# main_board.net
KiCad netlist of a schematic drawn in EAGLE
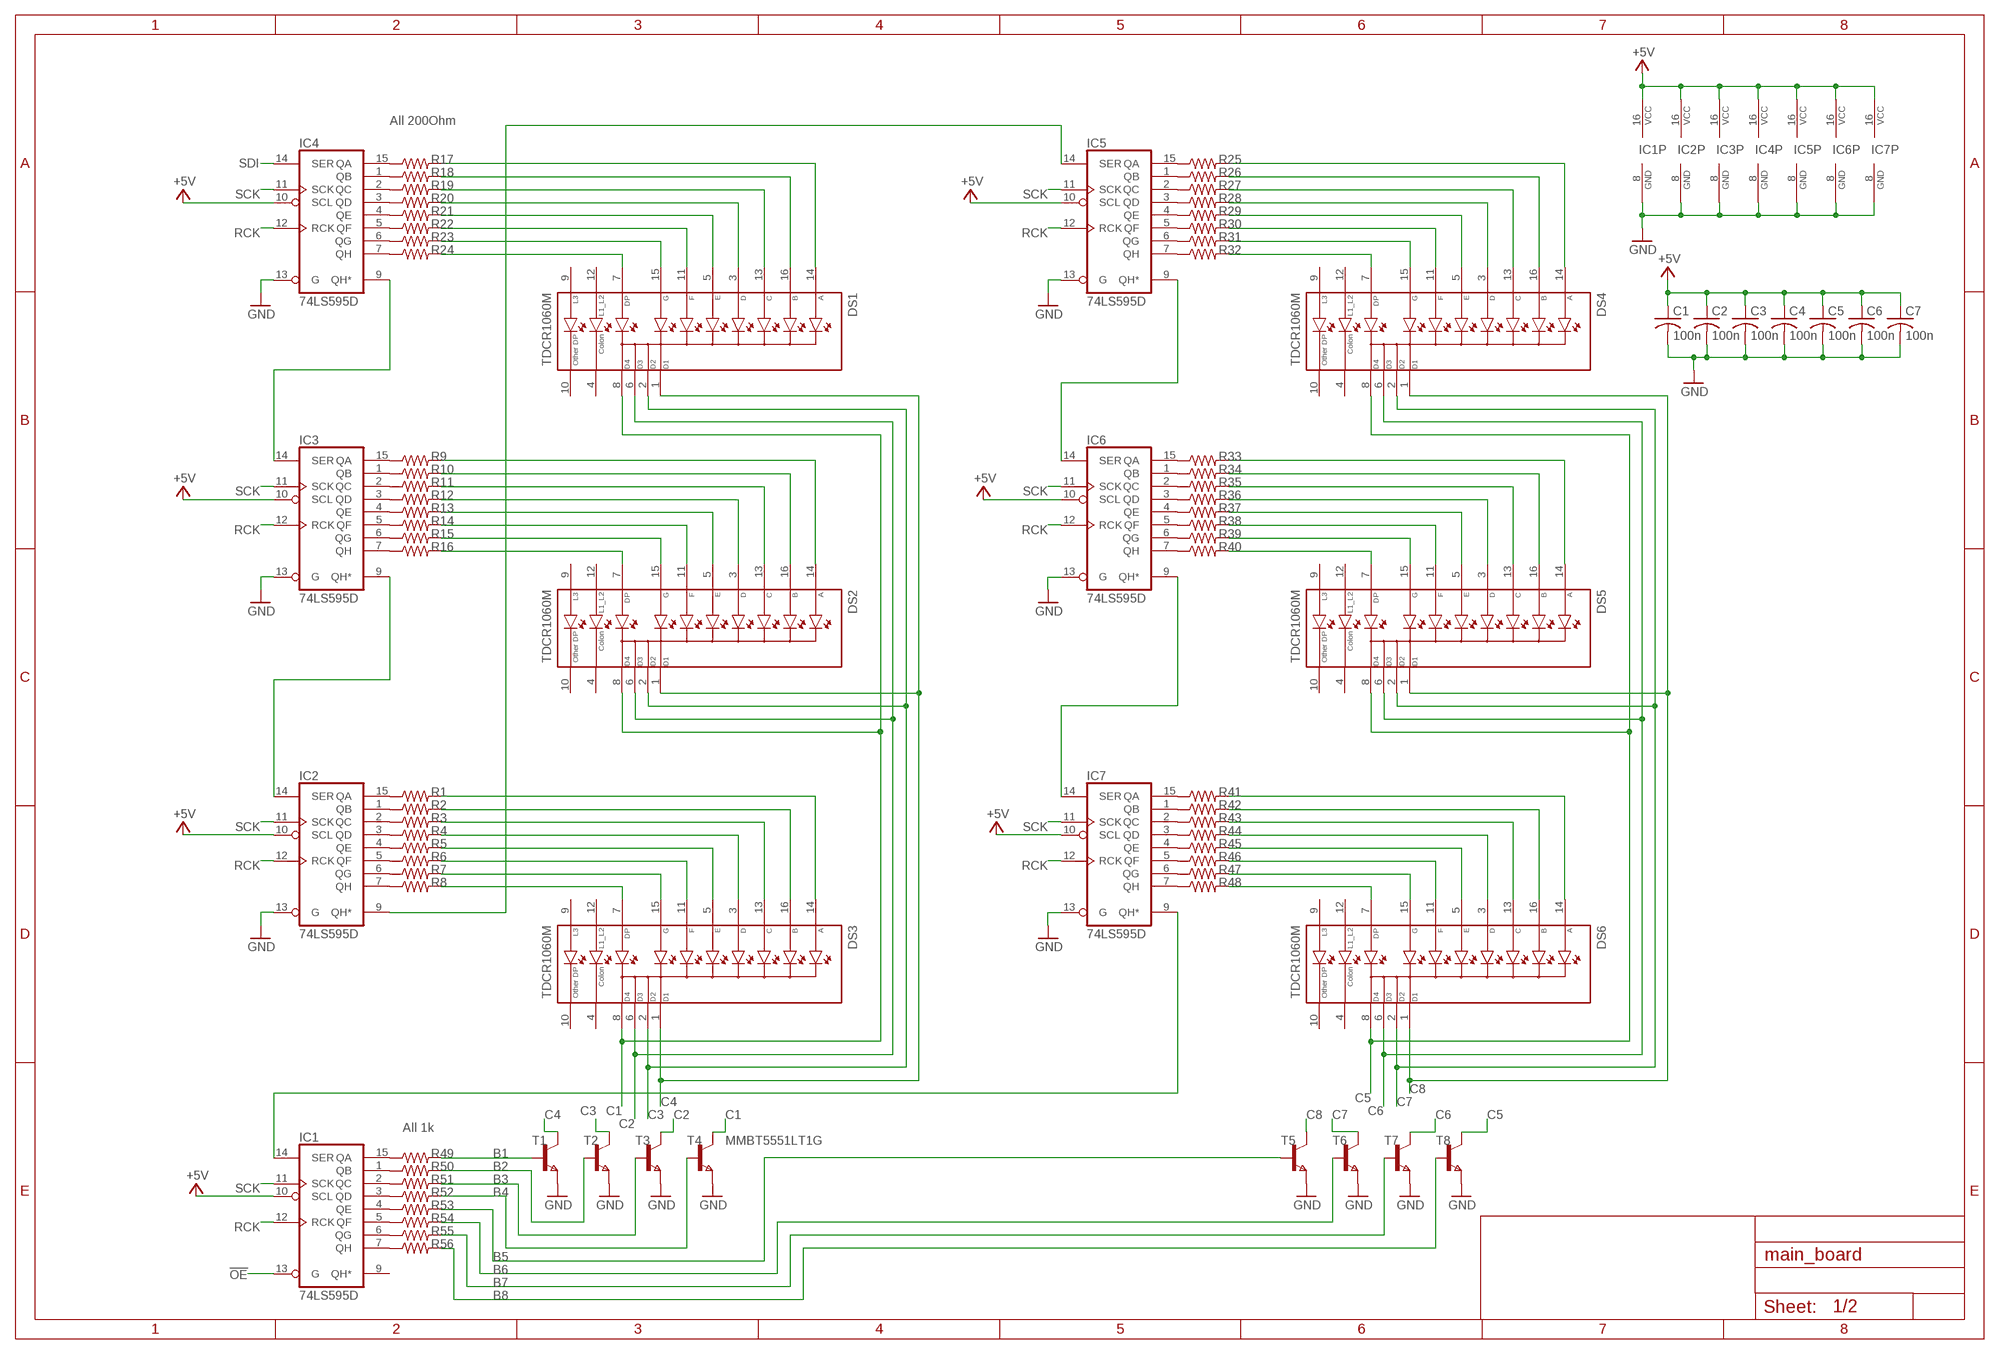
[diagram p0: schematic, sheet 1]
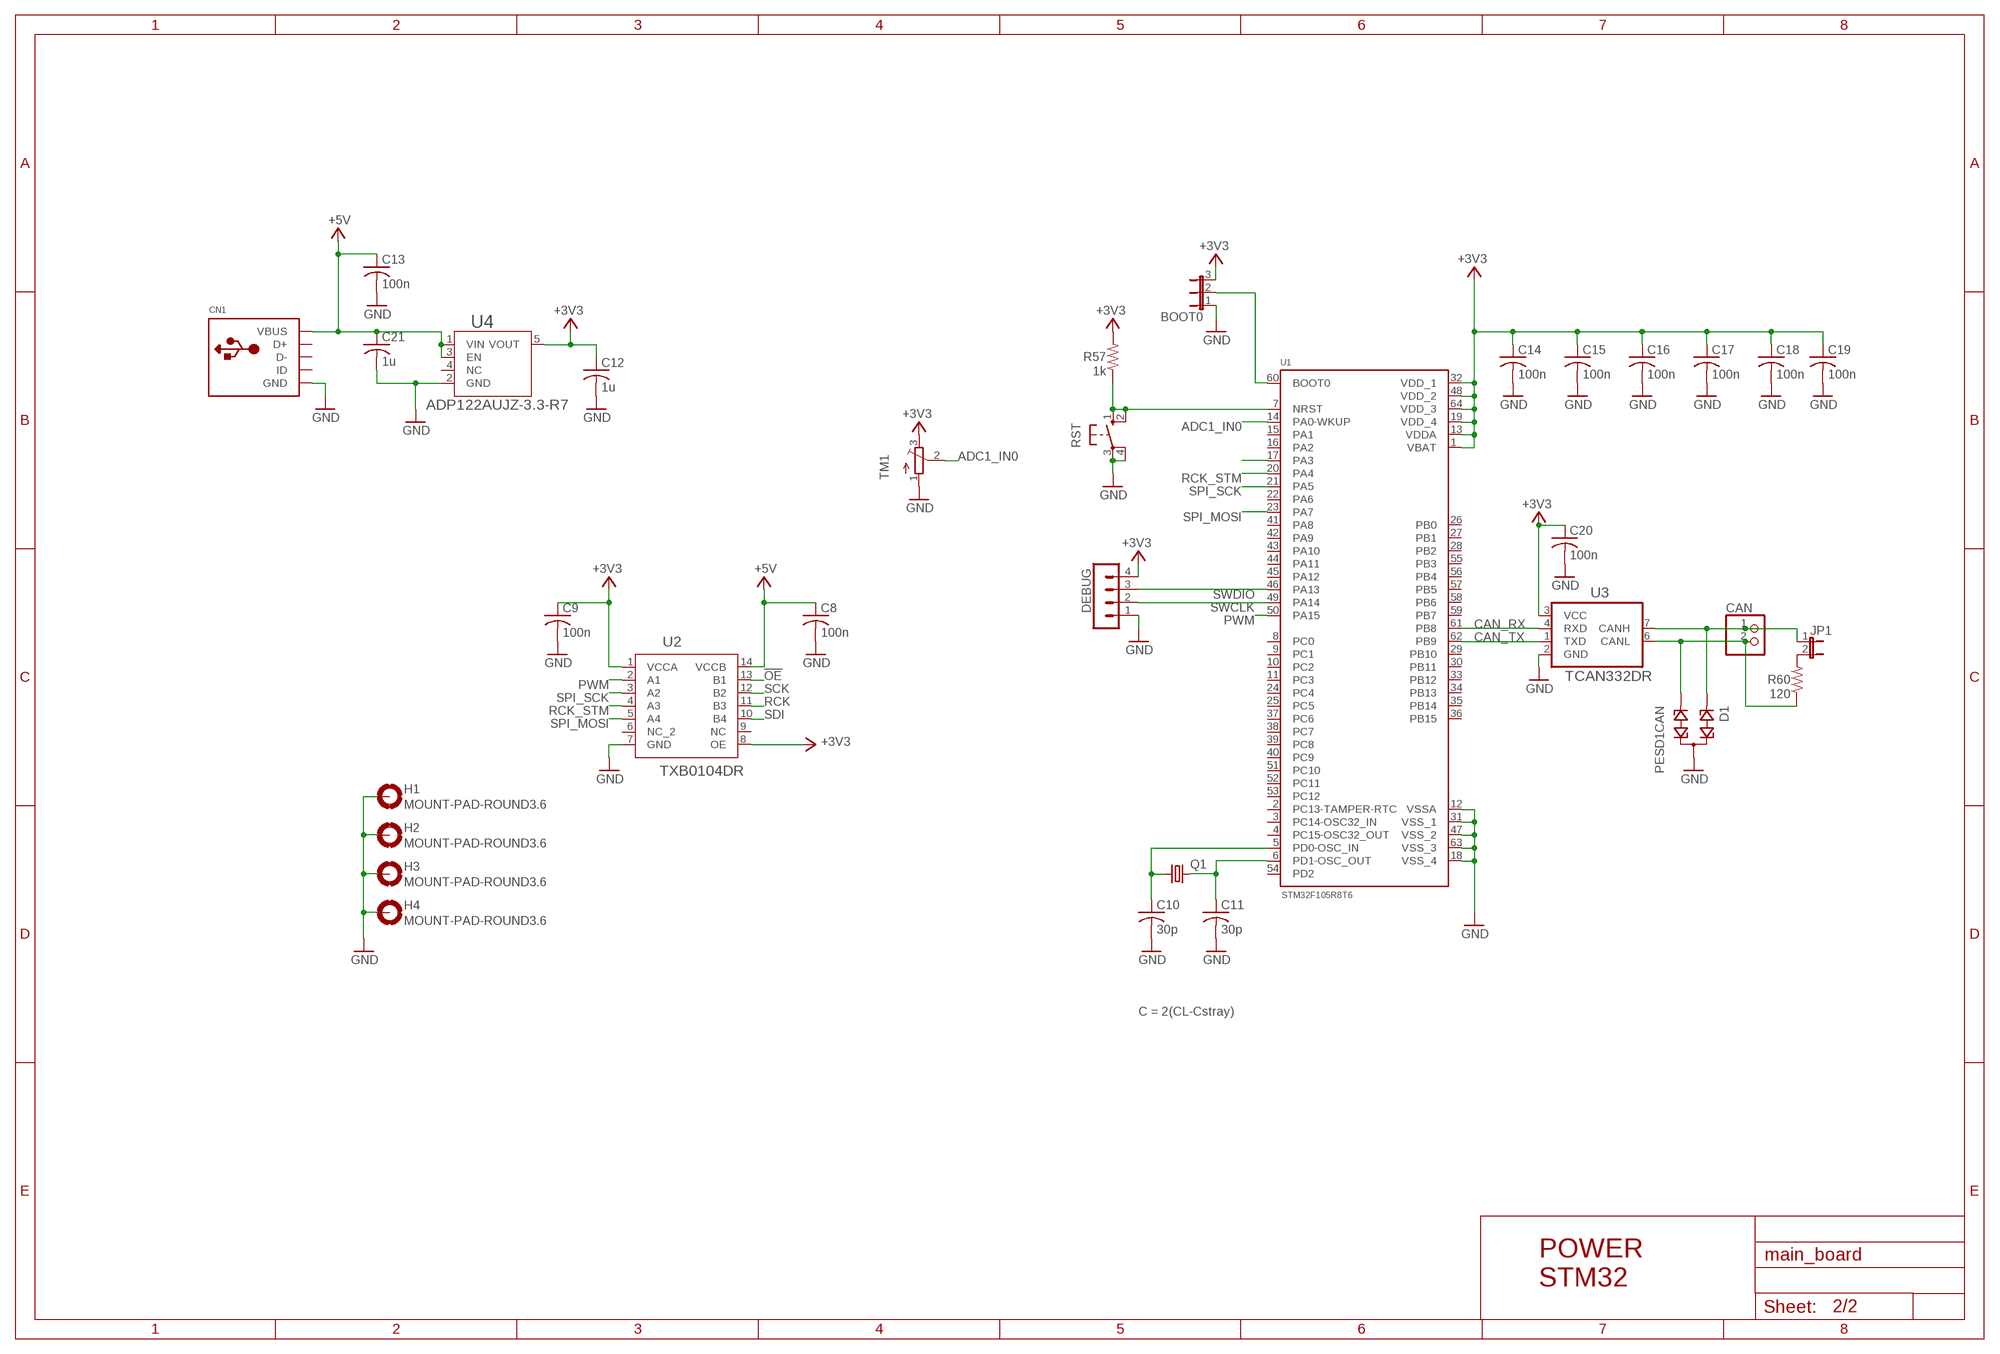
[diagram p1: schematic, sheet 2]

(export (version "E")
  (design (tool "Eeschema 10.0.6"))
  (components
    (comp (ref "C1")
      (value "100n")
      (footprint "eagle-import:C0603")
      (libsource (lib "eagle-import") (part "C-USC0603"))
    )
    (comp (ref "C2")
      (value "100n")
      (footprint "eagle-import:C0603")
      (libsource (lib "eagle-import") (part "C-USC0603"))
    )
    (comp (ref "C3")
      (value "100n")
      (footprint "eagle-import:C0603")
      (libsource (lib "eagle-import") (part "C-USC0603"))
    )
    (comp (ref "C4")
      (value "100n")
      (footprint "eagle-import:C0603")
      (libsource (lib "eagle-import") (part "C-USC0603"))
    )
    (comp (ref "C5")
      (value "100n")
      (footprint "eagle-import:C0603")
      (libsource (lib "eagle-import") (part "C-USC0603"))
    )
    (comp (ref "C6")
      (value "100n")
      (footprint "eagle-import:C0603")
      (libsource (lib "eagle-import") (part "C-USC0603"))
    )
    (comp (ref "C7")
      (value "100n")
      (footprint "eagle-import:C0603")
      (libsource (lib "eagle-import") (part "C-USC0603"))
    )
    (comp (ref "DS1")
      (value "TDCR1060M")
      (footprint "eagle-import:DISPLAY_TDCR1060M")
      (fields (field (name "DIGIKEY_PART_NUMBER") "TDCR1060M-ND") (field (name "MF") "Vishay Semiconductor"))
      (libsource (lib "eagle-import") (part "TDCR1060M"))
    )
    (comp (ref "DS2")
      (value "TDCR1060M")
      (footprint "eagle-import:DISPLAY_TDCR1060M")
      (fields (field (name "DIGIKEY_PART_NUMBER") "TDCR1060M-ND") (field (name "MF") "Vishay Semiconductor"))
      (libsource (lib "eagle-import") (part "TDCR1060M"))
    )
    (comp (ref "DS3")
      (value "TDCR1060M")
      (footprint "eagle-import:DISPLAY_TDCR1060M")
      (fields (field (name "DIGIKEY_PART_NUMBER") "TDCR1060M-ND") (field (name "MF") "Vishay Semiconductor"))
      (libsource (lib "eagle-import") (part "TDCR1060M"))
    )
    (comp (ref "DS4")
      (value "TDCR1060M")
      (footprint "eagle-import:DISPLAY_TDCR1060M")
      (fields (field (name "DIGIKEY_PART_NUMBER") "TDCR1060M-ND") (field (name "MF") "Vishay Semiconductor"))
      (libsource (lib "eagle-import") (part "TDCR1060M"))
    )
    (comp (ref "DS5")
      (value "TDCR1060M")
      (footprint "eagle-import:DISPLAY_TDCR1060M")
      (fields (field (name "DIGIKEY_PART_NUMBER") "TDCR1060M-ND") (field (name "MF") "Vishay Semiconductor"))
      (libsource (lib "eagle-import") (part "TDCR1060M"))
    )
    (comp (ref "DS6")
      (value "TDCR1060M")
      (footprint "eagle-import:DISPLAY_TDCR1060M")
      (fields (field (name "DIGIKEY_PART_NUMBER") "TDCR1060M-ND") (field (name "MF") "Vishay Semiconductor"))
      (libsource (lib "eagle-import") (part "TDCR1060M"))
    )
    (comp (ref "IC1")
      (value "74LS595D")
      (footprint "eagle-import:SO16")
      (libsource (lib "eagle-import") (part "74595DLS"))
    )
    (comp (ref "IC2")
      (value "74LS595D")
      (footprint "eagle-import:SO16")
      (libsource (lib "eagle-import") (part "74595DLS"))
    )
    (comp (ref "IC3")
      (value "74LS595D")
      (footprint "eagle-import:SO16")
      (libsource (lib "eagle-import") (part "74595DLS"))
    )
    (comp (ref "IC4")
      (value "74LS595D")
      (footprint "eagle-import:SO16")
      (libsource (lib "eagle-import") (part "74595DLS"))
    )
    (comp (ref "IC5")
      (value "74LS595D")
      (footprint "eagle-import:SO16")
      (libsource (lib "eagle-import") (part "74595DLS"))
    )
    (comp (ref "IC6")
      (value "74LS595D")
      (footprint "eagle-import:SO16")
      (libsource (lib "eagle-import") (part "74595DLS"))
    )
    (comp (ref "IC7")
      (value "74LS595D")
      (footprint "eagle-import:SO16")
      (libsource (lib "eagle-import") (part "74595DLS"))
    )
    (comp (ref "R1")
      (value "R-US_R0603")
      (footprint "eagle-import:R0603")
      (libsource (lib "eagle-import") (part "R-US_R0603"))
    )
    (comp (ref "R2")
      (value "R-US_R0603")
      (footprint "eagle-import:R0603")
      (libsource (lib "eagle-import") (part "R-US_R0603"))
    )
    (comp (ref "R3")
      (value "R-US_R0603")
      (footprint "eagle-import:R0603")
      (libsource (lib "eagle-import") (part "R-US_R0603"))
    )
    (comp (ref "R4")
      (value "R-US_R0603")
      (footprint "eagle-import:R0603")
      (libsource (lib "eagle-import") (part "R-US_R0603"))
    )
    (comp (ref "R5")
      (value "R-US_R0603")
      (footprint "eagle-import:R0603")
      (libsource (lib "eagle-import") (part "R-US_R0603"))
    )
    (comp (ref "R6")
      (value "R-US_R0603")
      (footprint "eagle-import:R0603")
      (libsource (lib "eagle-import") (part "R-US_R0603"))
    )
    (comp (ref "R7")
      (value "R-US_R0603")
      (footprint "eagle-import:R0603")
      (libsource (lib "eagle-import") (part "R-US_R0603"))
    )
    (comp (ref "R8")
      (value "R-US_R0603")
      (footprint "eagle-import:R0603")
      (libsource (lib "eagle-import") (part "R-US_R0603"))
    )
    (comp (ref "R9")
      (value "R-US_R0603")
      (footprint "eagle-import:R0603")
      (libsource (lib "eagle-import") (part "R-US_R0603"))
    )
    (comp (ref "R10")
      (value "R-US_R0603")
      (footprint "eagle-import:R0603")
      (libsource (lib "eagle-import") (part "R-US_R0603"))
    )
    (comp (ref "R11")
      (value "R-US_R0603")
      (footprint "eagle-import:R0603")
      (libsource (lib "eagle-import") (part "R-US_R0603"))
    )
    (comp (ref "R12")
      (value "R-US_R0603")
      (footprint "eagle-import:R0603")
      (libsource (lib "eagle-import") (part "R-US_R0603"))
    )
    (comp (ref "R13")
      (value "R-US_R0603")
      (footprint "eagle-import:R0603")
      (libsource (lib "eagle-import") (part "R-US_R0603"))
    )
    (comp (ref "R14")
      (value "R-US_R0603")
      (footprint "eagle-import:R0603")
      (libsource (lib "eagle-import") (part "R-US_R0603"))
    )
    (comp (ref "R15")
      (value "R-US_R0603")
      (footprint "eagle-import:R0603")
      (libsource (lib "eagle-import") (part "R-US_R0603"))
    )
    (comp (ref "R16")
      (value "R-US_R0603")
      (footprint "eagle-import:R0603")
      (libsource (lib "eagle-import") (part "R-US_R0603"))
    )
    (comp (ref "R17")
      (value "R-US_R0603")
      (footprint "eagle-import:R0603")
      (libsource (lib "eagle-import") (part "R-US_R0603"))
    )
    (comp (ref "R18")
      (value "R-US_R0603")
      (footprint "eagle-import:R0603")
      (libsource (lib "eagle-import") (part "R-US_R0603"))
    )
    (comp (ref "R19")
      (value "R-US_R0603")
      (footprint "eagle-import:R0603")
      (libsource (lib "eagle-import") (part "R-US_R0603"))
    )
    (comp (ref "R20")
      (value "R-US_R0603")
      (footprint "eagle-import:R0603")
      (libsource (lib "eagle-import") (part "R-US_R0603"))
    )
    (comp (ref "R21")
      (value "R-US_R0603")
      (footprint "eagle-import:R0603")
      (libsource (lib "eagle-import") (part "R-US_R0603"))
    )
    (comp (ref "R22")
      (value "R-US_R0603")
      (footprint "eagle-import:R0603")
      (libsource (lib "eagle-import") (part "R-US_R0603"))
    )
    (comp (ref "R23")
      (value "R-US_R0603")
      (footprint "eagle-import:R0603")
      (libsource (lib "eagle-import") (part "R-US_R0603"))
    )
    (comp (ref "R24")
      (value "R-US_R0603")
      (footprint "eagle-import:R0603")
      (libsource (lib "eagle-import") (part "R-US_R0603"))
    )
    (comp (ref "R25")
      (value "R-US_R0603")
      (footprint "eagle-import:R0603")
      (libsource (lib "eagle-import") (part "R-US_R0603"))
    )
    (comp (ref "R26")
      (value "R-US_R0603")
      (footprint "eagle-import:R0603")
      (libsource (lib "eagle-import") (part "R-US_R0603"))
    )
    (comp (ref "R27")
      (value "R-US_R0603")
      (footprint "eagle-import:R0603")
      (libsource (lib "eagle-import") (part "R-US_R0603"))
    )
    (comp (ref "R28")
      (value "R-US_R0603")
      (footprint "eagle-import:R0603")
      (libsource (lib "eagle-import") (part "R-US_R0603"))
    )
    (comp (ref "R29")
      (value "R-US_R0603")
      (footprint "eagle-import:R0603")
      (libsource (lib "eagle-import") (part "R-US_R0603"))
    )
    (comp (ref "R30")
      (value "R-US_R0603")
      (footprint "eagle-import:R0603")
      (libsource (lib "eagle-import") (part "R-US_R0603"))
    )
    (comp (ref "R31")
      (value "R-US_R0603")
      (footprint "eagle-import:R0603")
      (libsource (lib "eagle-import") (part "R-US_R0603"))
    )
    (comp (ref "R32")
      (value "R-US_R0603")
      (footprint "eagle-import:R0603")
      (libsource (lib "eagle-import") (part "R-US_R0603"))
    )
    (comp (ref "R33")
      (value "R-US_R0603")
      (footprint "eagle-import:R0603")
      (libsource (lib "eagle-import") (part "R-US_R0603"))
    )
    (comp (ref "R34")
      (value "R-US_R0603")
      (footprint "eagle-import:R0603")
      (libsource (lib "eagle-import") (part "R-US_R0603"))
    )
    (comp (ref "R35")
      (value "R-US_R0603")
      (footprint "eagle-import:R0603")
      (libsource (lib "eagle-import") (part "R-US_R0603"))
    )
    (comp (ref "R36")
      (value "R-US_R0603")
      (footprint "eagle-import:R0603")
      (libsource (lib "eagle-import") (part "R-US_R0603"))
    )
    (comp (ref "R37")
      (value "R-US_R0603")
      (footprint "eagle-import:R0603")
      (libsource (lib "eagle-import") (part "R-US_R0603"))
    )
    (comp (ref "R38")
      (value "R-US_R0603")
      (footprint "eagle-import:R0603")
      (libsource (lib "eagle-import") (part "R-US_R0603"))
    )
    (comp (ref "R39")
      (value "R-US_R0603")
      (footprint "eagle-import:R0603")
      (libsource (lib "eagle-import") (part "R-US_R0603"))
    )
    (comp (ref "R40")
      (value "R-US_R0603")
      (footprint "eagle-import:R0603")
      (libsource (lib "eagle-import") (part "R-US_R0603"))
    )
    (comp (ref "R41")
      (value "R-US_R0603")
      (footprint "eagle-import:R0603")
      (libsource (lib "eagle-import") (part "R-US_R0603"))
    )
    (comp (ref "R42")
      (value "R-US_R0603")
      (footprint "eagle-import:R0603")
      (libsource (lib "eagle-import") (part "R-US_R0603"))
    )
    (comp (ref "R43")
      (value "R-US_R0603")
      (footprint "eagle-import:R0603")
      (libsource (lib "eagle-import") (part "R-US_R0603"))
    )
    (comp (ref "R44")
      (value "R-US_R0603")
      (footprint "eagle-import:R0603")
      (libsource (lib "eagle-import") (part "R-US_R0603"))
    )
    (comp (ref "R45")
      (value "R-US_R0603")
      (footprint "eagle-import:R0603")
      (libsource (lib "eagle-import") (part "R-US_R0603"))
    )
    (comp (ref "R46")
      (value "R-US_R0603")
      (footprint "eagle-import:R0603")
      (libsource (lib "eagle-import") (part "R-US_R0603"))
    )
    (comp (ref "R47")
      (value "R-US_R0603")
      (footprint "eagle-import:R0603")
      (libsource (lib "eagle-import") (part "R-US_R0603"))
    )
    (comp (ref "R48")
      (value "R-US_R0603")
      (footprint "eagle-import:R0603")
      (libsource (lib "eagle-import") (part "R-US_R0603"))
    )
    (comp (ref "R49")
      (value "R-US_R0603")
      (footprint "eagle-import:R0603")
      (libsource (lib "eagle-import") (part "R-US_R0603"))
    )
    (comp (ref "R50")
      (value "R-US_R0603")
      (footprint "eagle-import:R0603")
      (libsource (lib "eagle-import") (part "R-US_R0603"))
    )
    (comp (ref "R51")
      (value "R-US_R0603")
      (footprint "eagle-import:R0603")
      (libsource (lib "eagle-import") (part "R-US_R0603"))
    )
    (comp (ref "R52")
      (value "R-US_R0603")
      (footprint "eagle-import:R0603")
      (libsource (lib "eagle-import") (part "R-US_R0603"))
    )
    (comp (ref "R53")
      (value "R-US_R0603")
      (footprint "eagle-import:R0603")
      (libsource (lib "eagle-import") (part "R-US_R0603"))
    )
    (comp (ref "R54")
      (value "R-US_R0603")
      (footprint "eagle-import:R0603")
      (libsource (lib "eagle-import") (part "R-US_R0603"))
    )
    (comp (ref "R55")
      (value "R-US_R0603")
      (footprint "eagle-import:R0603")
      (libsource (lib "eagle-import") (part "R-US_R0603"))
    )
    (comp (ref "R56")
      (value "R-US_R0603")
      (footprint "eagle-import:R0603")
      (libsource (lib "eagle-import") (part "R-US_R0603"))
    )
    (comp (ref "T1")
      (value "NPNSOT23")
      (footprint "eagle-import:SOT-23")
      (fields (field (name "MPN") "DSS20201L-7"))
      (libsource (lib "eagle-import") (part "NPNSOT23"))
    )
    (comp (ref "T2")
      (value "NPNSOT23")
      (footprint "eagle-import:SOT-23")
      (fields (field (name "MPN") "DSS20201L-7"))
      (libsource (lib "eagle-import") (part "NPNSOT23"))
    )
    (comp (ref "T3")
      (value "NPNSOT23")
      (footprint "eagle-import:SOT-23")
      (fields (field (name "MPN") "DSS20201L-7"))
      (libsource (lib "eagle-import") (part "NPNSOT23"))
    )
    (comp (ref "T4")
      (value "NPNSOT23")
      (footprint "eagle-import:SOT-23")
      (fields (field (name "MPN") "DSS20201L-7"))
      (libsource (lib "eagle-import") (part "NPNSOT23"))
    )
    (comp (ref "T5")
      (value "NPNSOT23")
      (footprint "eagle-import:SOT-23")
      (fields (field (name "MPN") "DSS20201L-7"))
      (libsource (lib "eagle-import") (part "NPNSOT23"))
    )
    (comp (ref "T6")
      (value "NPNSOT23")
      (footprint "eagle-import:SOT-23")
      (fields (field (name "MPN") "DSS20201L-7"))
      (libsource (lib "eagle-import") (part "NPNSOT23"))
    )
    (comp (ref "T7")
      (value "NPNSOT23")
      (footprint "eagle-import:SOT-23")
      (fields (field (name "MPN") "DSS20201L-7"))
      (libsource (lib "eagle-import") (part "NPNSOT23"))
    )
    (comp (ref "T8")
      (value "NPNSOT23")
      (footprint "eagle-import:SOT-23")
      (fields (field (name "MPN") "DSS20201L-7"))
      (libsource (lib "eagle-import") (part "NPNSOT23"))
    )
    (comp (ref "BOOT0")
      (value "JP2E")
      (footprint "eagle-import:JP2")
      (libsource (lib "eagle-import") (part "JP2E"))
    )
    (comp (ref "C8")
      (value "100n")
      (footprint "eagle-import:C0603")
      (libsource (lib "eagle-import") (part "C-USC0603"))
    )
    (comp (ref "C9")
      (value "100n")
      (footprint "eagle-import:C0603")
      (libsource (lib "eagle-import") (part "C-USC0603"))
    )
    (comp (ref "C10")
      (value "30p")
      (footprint "eagle-import:C0603")
      (libsource (lib "eagle-import") (part "C-USC0603"))
    )
    (comp (ref "C11")
      (value "30p")
      (footprint "eagle-import:C0603")
      (libsource (lib "eagle-import") (part "C-USC0603"))
    )
    (comp (ref "C12")
      (value "1u")
      (footprint "eagle-import:C0603")
      (libsource (lib "eagle-import") (part "C-USC0603"))
    )
    (comp (ref "C13")
      (value "100n")
      (footprint "eagle-import:C0603")
      (libsource (lib "eagle-import") (part "C-USC0603"))
    )
    (comp (ref "C14")
      (value "100n")
      (footprint "eagle-import:C0603")
      (libsource (lib "eagle-import") (part "C-USC0603"))
    )
    (comp (ref "C15")
      (value "100n")
      (footprint "eagle-import:C0603")
      (libsource (lib "eagle-import") (part "C-USC0603"))
    )
    (comp (ref "C16")
      (value "100n")
      (footprint "eagle-import:C0603")
      (libsource (lib "eagle-import") (part "C-USC0603"))
    )
    (comp (ref "C17")
      (value "100n")
      (footprint "eagle-import:C0603")
      (libsource (lib "eagle-import") (part "C-USC0603"))
    )
    (comp (ref "C18")
      (value "100n")
      (footprint "eagle-import:C0603")
      (libsource (lib "eagle-import") (part "C-USC0603"))
    )
    (comp (ref "C19")
      (value "100n")
      (footprint "eagle-import:C0603")
      (libsource (lib "eagle-import") (part "C-USC0603"))
    )
    (comp (ref "C20")
      (value "100n")
      (footprint "eagle-import:C0603")
      (libsource (lib "eagle-import") (part "C-USC0603"))
    )
    (comp (ref "C21")
      (value "1u")
      (footprint "eagle-import:C0603")
      (libsource (lib "eagle-import") (part "C-USC0603"))
    )
    (comp (ref "CAN")
      (value "PINHD-1X2")
      (footprint "eagle-import:1X02")
      (libsource (lib "eagle-import") (part "PINHD-1X2"))
    )
    (comp (ref "CN1")
      (value "USBMINIB")
      (footprint "eagle-import:USB-MINIB")
      (libsource (lib "eagle-import") (part "USBMINIB"))
    )
    (comp (ref "D1")
      (value "PESD1CAN")
      (footprint "eagle-import:SOT23")
      (libsource (lib "eagle-import") (part "PESD1CAN"))
    )
    (comp (ref "DEBUG")
      (value "MA04-1")
      (footprint "eagle-import:MA04-1")
      (libsource (lib "eagle-import") (part "MA04-1"))
    )
    (comp (ref "H1")
      (value "MOUNT-PAD-ROUND3.6")
      (footprint "eagle-import:3,6-PAD")
      (libsource (lib "eagle-import") (part "MOUNT-PAD-ROUND3.6"))
    )
    (comp (ref "H2")
      (value "MOUNT-PAD-ROUND3.6")
      (footprint "eagle-import:3,6-PAD")
      (libsource (lib "eagle-import") (part "MOUNT-PAD-ROUND3.6"))
    )
    (comp (ref "H3")
      (value "MOUNT-PAD-ROUND3.6")
      (footprint "eagle-import:3,6-PAD")
      (libsource (lib "eagle-import") (part "MOUNT-PAD-ROUND3.6"))
    )
    (comp (ref "H4")
      (value "MOUNT-PAD-ROUND3.6")
      (footprint "eagle-import:3,6-PAD")
      (libsource (lib "eagle-import") (part "MOUNT-PAD-ROUND3.6"))
    )
    (comp (ref "JP1")
      (value "JP1E")
      (footprint "eagle-import:JP1")
      (libsource (lib "eagle-import") (part "JP1E"))
    )
    (comp (ref "Q1")
      (value "CRYSTALHC49S")
      (footprint "eagle-import:HC49_S")
      (libsource (lib "eagle-import") (part "CRYSTALHC49S"))
    )
    (comp (ref "R57")
      (value "1k")
      (footprint "eagle-import:R0805")
      (libsource (lib "eagle-import") (part "R-US_R0805"))
    )
    (comp (ref "R60")
      (value "120")
      (footprint "eagle-import:R0805")
      (libsource (lib "eagle-import") (part "R-US_R0805"))
    )
    (comp (ref "RST")
      (value "10-XX")
      (footprint "eagle-import:B3F-10XX")
      (fields (field (name "MPN") "B3F-1000"))
      (libsource (lib "eagle-import") (part "10-XX"))
    )
    (comp (ref "TM1")
      (value "TRIMPOT3386")
      (footprint "eagle-import:TRIM-3386")
      (libsource (lib "eagle-import") (part "TRIMPOT3386"))
    )
    (comp (ref "U1")
      (value "STM32F105R8T6")
      (footprint "eagle-import:QFP50P1200X1200X160-64N")
      (fields (field (name "DIGIKEY_PART_NUMBER") "497-8922-ND") (field (name "MF") "STMicroelectronics"))
      (libsource (lib "eagle-import") (part "STM32F105R8T6"))
    )
    (comp (ref "U2")
      (value "TXB0104DR")
      (footprint "eagle-import:D14")
      (fields (field (name "COPYRIGHT") "Copyright (C) 2023 Ultra Librarian. All rights reserved."))
      (libsource (lib "eagle-import") (part "TXB0104DR"))
    )
    (comp (ref "U3")
      (value "TCAN332DR")
      (footprint "eagle-import:SOIC127P599X175-8N")
      (fields (field (name "MF") "Texas Instruments"))
      (libsource (lib "eagle-import") (part "TCAN332DR"))
    )
    (comp (ref "U4")
      (value "ADP122AUJZ-3.3-R7")
      (footprint "eagle-import:SOT95P280X100-5N")
      (libsource (lib "eagle-import") (part "ADP122AUJZ-3.3-R7"))
    )
  )
  (nets
    (net (code "1") (name "+3V3") (class "Default")
      (node (ref "BOOT0") (pin "3") (pinfunction "3_3") (pintype "passive"))
      (node (ref "C12") (pin "1") (pinfunction "1_1") (pintype "passive"))
      (node (ref "C14") (pin "1") (pinfunction "1_1") (pintype "passive"))
      (node (ref "C15") (pin "1") (pinfunction "1_1") (pintype "passive"))
      (node (ref "C16") (pin "1") (pinfunction "1_1") (pintype "passive"))
      (node (ref "C17") (pin "1") (pinfunction "1_1") (pintype "passive"))
      (node (ref "C18") (pin "1") (pinfunction "1_1") (pintype "passive"))
      (node (ref "C19") (pin "1") (pinfunction "1_1") (pintype "passive"))
      (node (ref "C20") (pin "1") (pinfunction "1_1") (pintype "passive"))
      (node (ref "C9") (pin "1") (pinfunction "1_1") (pintype "passive"))
      (node (ref "DEBUG") (pin "4") (pinfunction "4_4") (pintype "passive"))
      (node (ref "R57") (pin "2") (pinfunction "2_2") (pintype "passive"))
      (node (ref "TM1") (pin "3") (pinfunction "E_3") (pintype "passive"))
      (node (ref "U1") (pin "1") (pinfunction "VBAT_1") (pintype "power_in"))
      (node (ref "U1") (pin "13") (pinfunction "VDDA_13") (pintype "power_in"))
      (node (ref "U1") (pin "19") (pinfunction "VDD_4_19") (pintype "power_in"))
      (node (ref "U1") (pin "32") (pinfunction "VDD_1_32") (pintype "power_in"))
      (node (ref "U1") (pin "48") (pinfunction "VDD_2_48") (pintype "power_in"))
      (node (ref "U1") (pin "64") (pinfunction "VDD_3_64") (pintype "power_in"))
      (node (ref "U2") (pin "1") (pinfunction "VCCA_1") (pintype "power_in"))
      (node (ref "U2") (pin "8") (pinfunction "OE_8") (pintype "output"))
      (node (ref "U3") (pin "3") (pinfunction "VCC_3") (pintype "power_in"))
      (node (ref "U4") (pin "5") (pinfunction "VOUT_5") (pintype "output"))
    )
    (net (code "2") (name "+5V") (class "Default")
      (node (ref "C1") (pin "1") (pinfunction "1_1") (pintype "passive"))
      (node (ref "C13") (pin "1") (pinfunction "1_1") (pintype "passive"))
      (node (ref "C2") (pin "1") (pinfunction "1_1") (pintype "passive"))
      (node (ref "C21") (pin "1") (pinfunction "1_1") (pintype "passive"))
      (node (ref "C3") (pin "1") (pinfunction "1_1") (pintype "passive"))
      (node (ref "C4") (pin "1") (pinfunction "1_1") (pintype "passive"))
      (node (ref "C5") (pin "1") (pinfunction "1_1") (pintype "passive"))
      (node (ref "C6") (pin "1") (pinfunction "1_1") (pintype "passive"))
      (node (ref "C7") (pin "1") (pinfunction "1_1") (pintype "passive"))
      (node (ref "C8") (pin "1") (pinfunction "1_1") (pintype "passive"))
      (node (ref "CN1") (pin "VBUS") (pinfunction "VBUS_VBUS") (pintype "power_in"))
      (node (ref "IC1") (pin "10") (pinfunction "SCL_10") (pintype "input"))
      (node (ref "IC1") (pin "16") (pinfunction "VCC_16") (pintype "power_in"))
      (node (ref "IC2") (pin "10") (pinfunction "SCL_10") (pintype "input"))
      (node (ref "IC2") (pin "16") (pinfunction "VCC_16") (pintype "power_in"))
      (node (ref "IC3") (pin "10") (pinfunction "SCL_10") (pintype "input"))
      (node (ref "IC3") (pin "16") (pinfunction "VCC_16") (pintype "power_in"))
      (node (ref "IC4") (pin "10") (pinfunction "SCL_10") (pintype "input"))
      (node (ref "IC4") (pin "16") (pinfunction "VCC_16") (pintype "power_in"))
      (node (ref "IC5") (pin "10") (pinfunction "SCL_10") (pintype "input"))
      (node (ref "IC5") (pin "16") (pinfunction "VCC_16") (pintype "power_in"))
      (node (ref "IC6") (pin "10") (pinfunction "SCL_10") (pintype "input"))
      (node (ref "IC6") (pin "16") (pinfunction "VCC_16") (pintype "power_in"))
      (node (ref "IC7") (pin "10") (pinfunction "SCL_10") (pintype "input"))
      (node (ref "IC7") (pin "16") (pinfunction "VCC_16") (pintype "power_in"))
      (node (ref "U2") (pin "14") (pinfunction "VCCB_14") (pintype "power_in"))
      (node (ref "U4") (pin "1") (pinfunction "VIN_1") (pintype "power_in"))
      (node (ref "U4") (pin "3") (pinfunction "EN_3") (pintype "input"))
    )
    (net (code "3") (name "ADC1_IN0") (class "Default")
      (node (ref "TM1") (pin "2") (pinfunction "S_2") (pintype "passive"))
      (node (ref "U1") (pin "14") (pinfunction "PA0-WKUP_14") (pintype "bidirectional"))
    )
    (net (code "4") (name "B1") (class "Default")
      (node (ref "R49") (pin "2") (pinfunction "2_2") (pintype "passive"))
      (node (ref "T1") (pin "3") (pinfunction "B_3") (pintype "passive"))
    )
    (net (code "5") (name "B2") (class "Default")
      (node (ref "R50") (pin "2") (pinfunction "2_2") (pintype "passive"))
      (node (ref "T2") (pin "3") (pinfunction "B_3") (pintype "passive"))
    )
    (net (code "6") (name "B3") (class "Default")
      (node (ref "R51") (pin "2") (pinfunction "2_2") (pintype "passive"))
      (node (ref "T3") (pin "3") (pinfunction "B_3") (pintype "passive"))
    )
    (net (code "7") (name "B4") (class "Default")
      (node (ref "R52") (pin "2") (pinfunction "2_2") (pintype "passive"))
      (node (ref "T4") (pin "3") (pinfunction "B_3") (pintype "passive"))
    )
    (net (code "8") (name "B5") (class "Default")
      (node (ref "R53") (pin "2") (pinfunction "2_2") (pintype "passive"))
      (node (ref "T5") (pin "3") (pinfunction "B_3") (pintype "passive"))
    )
    (net (code "9") (name "B6") (class "Default")
      (node (ref "R54") (pin "2") (pinfunction "2_2") (pintype "passive"))
      (node (ref "T6") (pin "3") (pinfunction "B_3") (pintype "passive"))
    )
    (net (code "10") (name "B7") (class "Default")
      (node (ref "R55") (pin "2") (pinfunction "2_2") (pintype "passive"))
      (node (ref "T7") (pin "3") (pinfunction "B_3") (pintype "passive"))
    )
    (net (code "11") (name "B8") (class "Default")
      (node (ref "R56") (pin "2") (pinfunction "2_2") (pintype "passive"))
      (node (ref "T8") (pin "3") (pinfunction "B_3") (pintype "passive"))
    )
    (net (code "12") (name "C1") (class "Default")
      (node (ref "DS1") (pin "8") (pinfunction "D4_8") (pintype "passive"))
      (node (ref "DS2") (pin "8") (pinfunction "D4_8") (pintype "passive"))
      (node (ref "DS3") (pin "8") (pinfunction "D4_8") (pintype "passive"))
      (node (ref "T4") (pin "1") (pinfunction "C_1") (pintype "passive"))
    )
    (net (code "13") (name "C2") (class "Default")
      (node (ref "DS1") (pin "6") (pinfunction "D3_6") (pintype "passive"))
      (node (ref "DS2") (pin "6") (pinfunction "D3_6") (pintype "passive"))
      (node (ref "DS3") (pin "6") (pinfunction "D3_6") (pintype "passive"))
      (node (ref "T3") (pin "1") (pinfunction "C_1") (pintype "passive"))
    )
    (net (code "14") (name "C3") (class "Default")
      (node (ref "DS1") (pin "2") (pinfunction "D2_2") (pintype "passive"))
      (node (ref "DS2") (pin "2") (pinfunction "D2_2") (pintype "passive"))
      (node (ref "DS3") (pin "2") (pinfunction "D2_2") (pintype "passive"))
      (node (ref "T2") (pin "1") (pinfunction "C_1") (pintype "passive"))
    )
    (net (code "15") (name "C4") (class "Default")
      (node (ref "DS1") (pin "1") (pinfunction "D1_1") (pintype "passive"))
      (node (ref "DS2") (pin "1") (pinfunction "D1_1") (pintype "passive"))
      (node (ref "DS3") (pin "1") (pinfunction "D1_1") (pintype "passive"))
      (node (ref "T1") (pin "1") (pinfunction "C_1") (pintype "passive"))
    )
    (net (code "16") (name "C5") (class "Default")
      (node (ref "DS4") (pin "8") (pinfunction "D4_8") (pintype "passive"))
      (node (ref "DS5") (pin "8") (pinfunction "D4_8") (pintype "passive"))
      (node (ref "DS6") (pin "8") (pinfunction "D4_8") (pintype "passive"))
      (node (ref "T8") (pin "1") (pinfunction "C_1") (pintype "passive"))
    )
    (net (code "17") (name "C6") (class "Default")
      (node (ref "DS4") (pin "6") (pinfunction "D3_6") (pintype "passive"))
      (node (ref "DS5") (pin "6") (pinfunction "D3_6") (pintype "passive"))
      (node (ref "DS6") (pin "6") (pinfunction "D3_6") (pintype "passive"))
      (node (ref "T7") (pin "1") (pinfunction "C_1") (pintype "passive"))
    )
    (net (code "18") (name "C7") (class "Default")
      (node (ref "DS4") (pin "2") (pinfunction "D2_2") (pintype "passive"))
      (node (ref "DS5") (pin "2") (pinfunction "D2_2") (pintype "passive"))
      (node (ref "DS6") (pin "2") (pinfunction "D2_2") (pintype "passive"))
      (node (ref "T6") (pin "1") (pinfunction "C_1") (pintype "passive"))
    )
    (net (code "19") (name "C8") (class "Default")
      (node (ref "DS4") (pin "1") (pinfunction "D1_1") (pintype "passive"))
      (node (ref "DS5") (pin "1") (pinfunction "D1_1") (pintype "passive"))
      (node (ref "DS6") (pin "1") (pinfunction "D1_1") (pintype "passive"))
      (node (ref "T5") (pin "1") (pinfunction "C_1") (pintype "passive"))
    )
    (net (code "20") (name "CAN_RX") (class "Default")
      (node (ref "U1") (pin "61") (pinfunction "PB8_61") (pintype "bidirectional"))
      (node (ref "U3") (pin "4") (pinfunction "RXD_4") (pintype "bidirectional"))
    )
    (net (code "21") (name "CAN_TX") (class "Default")
      (node (ref "U1") (pin "62") (pinfunction "PB9_62") (pintype "bidirectional"))
      (node (ref "U3") (pin "1") (pinfunction "TXD_1") (pintype "bidirectional"))
    )
    (net (code "22") (name "GND") (class "Default")
      (node (ref "BOOT0") (pin "1") (pinfunction "1_1") (pintype "passive"))
      (node (ref "C1") (pin "2") (pinfunction "2_2") (pintype "passive"))
      (node (ref "C10") (pin "2") (pinfunction "2_2") (pintype "passive"))
      (node (ref "C11") (pin "2") (pinfunction "2_2") (pintype "passive"))
      (node (ref "C12") (pin "2") (pinfunction "2_2") (pintype "passive"))
      (node (ref "C13") (pin "2") (pinfunction "2_2") (pintype "passive"))
      (node (ref "C14") (pin "2") (pinfunction "2_2") (pintype "passive"))
      (node (ref "C15") (pin "2") (pinfunction "2_2") (pintype "passive"))
      (node (ref "C16") (pin "2") (pinfunction "2_2") (pintype "passive"))
      (node (ref "C17") (pin "2") (pinfunction "2_2") (pintype "passive"))
      (node (ref "C18") (pin "2") (pinfunction "2_2") (pintype "passive"))
      (node (ref "C19") (pin "2") (pinfunction "2_2") (pintype "passive"))
      (node (ref "C2") (pin "2") (pinfunction "2_2") (pintype "passive"))
      (node (ref "C20") (pin "2") (pinfunction "2_2") (pintype "passive"))
      (node (ref "C21") (pin "2") (pinfunction "2_2") (pintype "passive"))
      (node (ref "C3") (pin "2") (pinfunction "2_2") (pintype "passive"))
      (node (ref "C4") (pin "2") (pinfunction "2_2") (pintype "passive"))
      (node (ref "C5") (pin "2") (pinfunction "2_2") (pintype "passive"))
      (node (ref "C6") (pin "2") (pinfunction "2_2") (pintype "passive"))
      (node (ref "C7") (pin "2") (pinfunction "2_2") (pintype "passive"))
      (node (ref "C8") (pin "2") (pinfunction "2_2") (pintype "passive"))
      (node (ref "C9") (pin "2") (pinfunction "2_2") (pintype "passive"))
      (node (ref "CN1") (pin "GND") (pinfunction "GND_GND") (pintype "power_in"))
      (node (ref "D1") (pin "3") (pinfunction "3_3") (pintype "passive"))
      (node (ref "DEBUG") (pin "1") (pinfunction "1_1") (pintype "passive"))
      (node (ref "H1") (pin "B3,6") (pinfunction "MOUNT_B3,6") (pintype "passive"))
      (node (ref "H2") (pin "B3,6") (pinfunction "MOUNT_B3,6") (pintype "passive"))
      (node (ref "H3") (pin "B3,6") (pinfunction "MOUNT_B3,6") (pintype "passive"))
      (node (ref "H4") (pin "B3,6") (pinfunction "MOUNT_B3,6") (pintype "passive"))
      (node (ref "IC1") (pin "8") (pinfunction "GND_8") (pintype "power_in"))
      (node (ref "IC2") (pin "13") (pinfunction "G_13") (pintype "input"))
      (node (ref "IC2") (pin "8") (pinfunction "GND_8") (pintype "power_in"))
      (node (ref "IC3") (pin "13") (pinfunction "G_13") (pintype "input"))
      (node (ref "IC3") (pin "8") (pinfunction "GND_8") (pintype "power_in"))
      (node (ref "IC4") (pin "13") (pinfunction "G_13") (pintype "input"))
      (node (ref "IC4") (pin "8") (pinfunction "GND_8") (pintype "power_in"))
      (node (ref "IC5") (pin "13") (pinfunction "G_13") (pintype "input"))
      (node (ref "IC5") (pin "8") (pinfunction "GND_8") (pintype "power_in"))
      (node (ref "IC6") (pin "13") (pinfunction "G_13") (pintype "input"))
      (node (ref "IC6") (pin "8") (pinfunction "GND_8") (pintype "power_in"))
      (node (ref "IC7") (pin "13") (pinfunction "G_13") (pintype "input"))
      (node (ref "IC7") (pin "8") (pinfunction "GND_8") (pintype "power_in"))
      (node (ref "RST") (pin "3") (pinfunction "P_3") (pintype "passive"))
      (node (ref "RST") (pin "4") (pinfunction "P1_4") (pintype "passive"))
      (node (ref "T1") (pin "2") (pinfunction "E_2") (pintype "passive"))
      (node (ref "T2") (pin "2") (pinfunction "E_2") (pintype "passive"))
      (node (ref "T3") (pin "2") (pinfunction "E_2") (pintype "passive"))
      (node (ref "T4") (pin "2") (pinfunction "E_2") (pintype "passive"))
      (node (ref "T5") (pin "2") (pinfunction "E_2") (pintype "passive"))
      (node (ref "T6") (pin "2") (pinfunction "E_2") (pintype "passive"))
      (node (ref "T7") (pin "2") (pinfunction "E_2") (pintype "passive"))
      (node (ref "T8") (pin "2") (pinfunction "E_2") (pintype "passive"))
      (node (ref "TM1") (pin "1") (pinfunction "A_1") (pintype "passive"))
      (node (ref "U1") (pin "12") (pinfunction "VSSA_12") (pintype "power_in"))
      (node (ref "U1") (pin "18") (pinfunction "VSS_4_18") (pintype "power_in"))
      (node (ref "U1") (pin "31") (pinfunction "VSS_1_31") (pintype "power_in"))
      (node (ref "U1") (pin "47") (pinfunction "VSS_2_47") (pintype "power_in"))
      (node (ref "U1") (pin "63") (pinfunction "VSS_3_63") (pintype "power_in"))
      (node (ref "U2") (pin "7") (pinfunction "GND_7") (pintype "power_in"))
      (node (ref "U3") (pin "2") (pinfunction "GND_2") (pintype "power_in"))
      (node (ref "U4") (pin "2") (pinfunction "GND_2") (pintype "passive"))
    )
    (net (code "23") (name "Net-(DS1-A)") (class "Default")
      (node (ref "DS1") (pin "14") (pinfunction "A_14") (pintype "passive"))
      (node (ref "R17") (pin "2") (pinfunction "2_2") (pintype "passive"))
    )
    (net (code "24") (name "Net-(DS1-B)") (class "Default")
      (node (ref "DS1") (pin "16") (pinfunction "B_16") (pintype "passive"))
      (node (ref "R18") (pin "2") (pinfunction "2_2") (pintype "passive"))
    )
    (net (code "25") (name "Net-(DS1-C)") (class "Default")
      (node (ref "DS1") (pin "13") (pinfunction "C_13") (pintype "passive"))
      (node (ref "R19") (pin "2") (pinfunction "2_2") (pintype "passive"))
    )
    (net (code "26") (name "Net-(DS1-D)") (class "Default")
      (node (ref "DS1") (pin "3") (pinfunction "D_3") (pintype "passive"))
      (node (ref "R20") (pin "2") (pinfunction "2_2") (pintype "passive"))
    )
    (net (code "27") (name "Net-(DS1-DP)") (class "Default")
      (node (ref "DS1") (pin "7") (pinfunction "DP_7") (pintype "passive"))
      (node (ref "R24") (pin "2") (pinfunction "2_2") (pintype "passive"))
    )
    (net (code "28") (name "Net-(DS1-E)") (class "Default")
      (node (ref "DS1") (pin "5") (pinfunction "E_5") (pintype "passive"))
      (node (ref "R21") (pin "2") (pinfunction "2_2") (pintype "passive"))
    )
    (net (code "29") (name "Net-(DS1-F)") (class "Default")
      (node (ref "DS1") (pin "11") (pinfunction "F_11") (pintype "passive"))
      (node (ref "R22") (pin "2") (pinfunction "2_2") (pintype "passive"))
    )
    (net (code "30") (name "Net-(DS1-G)") (class "Default")
      (node (ref "DS1") (pin "15") (pinfunction "G_15") (pintype "passive"))
      (node (ref "R23") (pin "2") (pinfunction "2_2") (pintype "passive"))
    )
    (net (code "31") (name "Net-(DS2-A)") (class "Default")
      (node (ref "DS2") (pin "14") (pinfunction "A_14") (pintype "passive"))
      (node (ref "R9") (pin "2") (pinfunction "2_2") (pintype "passive"))
    )
    (net (code "32") (name "Net-(DS2-B)") (class "Default")
      (node (ref "DS2") (pin "16") (pinfunction "B_16") (pintype "passive"))
      (node (ref "R10") (pin "2") (pinfunction "2_2") (pintype "passive"))
    )
    (net (code "33") (name "Net-(DS2-C)") (class "Default")
      (node (ref "DS2") (pin "13") (pinfunction "C_13") (pintype "passive"))
      (node (ref "R11") (pin "2") (pinfunction "2_2") (pintype "passive"))
    )
    (net (code "34") (name "Net-(DS2-D)") (class "Default")
      (node (ref "DS2") (pin "3") (pinfunction "D_3") (pintype "passive"))
      (node (ref "R12") (pin "2") (pinfunction "2_2") (pintype "passive"))
    )
    (net (code "35") (name "Net-(DS2-DP)") (class "Default")
      (node (ref "DS2") (pin "7") (pinfunction "DP_7") (pintype "passive"))
      (node (ref "R16") (pin "2") (pinfunction "2_2") (pintype "passive"))
    )
    (net (code "36") (name "Net-(DS2-E)") (class "Default")
      (node (ref "DS2") (pin "5") (pinfunction "E_5") (pintype "passive"))
      (node (ref "R13") (pin "2") (pinfunction "2_2") (pintype "passive"))
    )
    (net (code "37") (name "Net-(DS2-F)") (class "Default")
      (node (ref "DS2") (pin "11") (pinfunction "F_11") (pintype "passive"))
      (node (ref "R14") (pin "2") (pinfunction "2_2") (pintype "passive"))
    )
    (net (code "38") (name "Net-(DS2-G)") (class "Default")
      (node (ref "DS2") (pin "15") (pinfunction "G_15") (pintype "passive"))
      (node (ref "R15") (pin "2") (pinfunction "2_2") (pintype "passive"))
    )
    (net (code "39") (name "Net-(DS3-A)") (class "Default")
      (node (ref "DS3") (pin "14") (pinfunction "A_14") (pintype "passive"))
      (node (ref "R1") (pin "2") (pinfunction "2_2") (pintype "passive"))
    )
    (net (code "40") (name "Net-(DS3-B)") (class "Default")
      (node (ref "DS3") (pin "16") (pinfunction "B_16") (pintype "passive"))
      (node (ref "R2") (pin "2") (pinfunction "2_2") (pintype "passive"))
    )
    (net (code "41") (name "Net-(DS3-C)") (class "Default")
      (node (ref "DS3") (pin "13") (pinfunction "C_13") (pintype "passive"))
      (node (ref "R3") (pin "2") (pinfunction "2_2") (pintype "passive"))
    )
    (net (code "42") (name "Net-(DS3-D)") (class "Default")
      (node (ref "DS3") (pin "3") (pinfunction "D_3") (pintype "passive"))
      (node (ref "R4") (pin "2") (pinfunction "2_2") (pintype "passive"))
    )
    (net (code "43") (name "Net-(DS3-DP)") (class "Default")
      (node (ref "DS3") (pin "7") (pinfunction "DP_7") (pintype "passive"))
      (node (ref "R8") (pin "2") (pinfunction "2_2") (pintype "passive"))
    )
    (net (code "44") (name "Net-(DS3-E)") (class "Default")
      (node (ref "DS3") (pin "5") (pinfunction "E_5") (pintype "passive"))
      (node (ref "R5") (pin "2") (pinfunction "2_2") (pintype "passive"))
    )
    (net (code "45") (name "Net-(DS3-F)") (class "Default")
      (node (ref "DS3") (pin "11") (pinfunction "F_11") (pintype "passive"))
      (node (ref "R6") (pin "2") (pinfunction "2_2") (pintype "passive"))
    )
    (net (code "46") (name "Net-(DS3-G)") (class "Default")
      (node (ref "DS3") (pin "15") (pinfunction "G_15") (pintype "passive"))
      (node (ref "R7") (pin "2") (pinfunction "2_2") (pintype "passive"))
    )
    (net (code "47") (name "Net-(DS4-A)") (class "Default")
      (node (ref "DS4") (pin "14") (pinfunction "A_14") (pintype "passive"))
      (node (ref "R25") (pin "2") (pinfunction "2_2") (pintype "passive"))
    )
    (net (code "48") (name "Net-(DS4-B)") (class "Default")
      (node (ref "DS4") (pin "16") (pinfunction "B_16") (pintype "passive"))
      (node (ref "R26") (pin "2") (pinfunction "2_2") (pintype "passive"))
    )
    (net (code "49") (name "Net-(DS4-C)") (class "Default")
      (node (ref "DS4") (pin "13") (pinfunction "C_13") (pintype "passive"))
      (node (ref "R27") (pin "2") (pinfunction "2_2") (pintype "passive"))
    )
    (net (code "50") (name "Net-(DS4-D)") (class "Default")
      (node (ref "DS4") (pin "3") (pinfunction "D_3") (pintype "passive"))
      (node (ref "R28") (pin "2") (pinfunction "2_2") (pintype "passive"))
    )
    (net (code "51") (name "Net-(DS4-DP)") (class "Default")
      (node (ref "DS4") (pin "7") (pinfunction "DP_7") (pintype "passive"))
      (node (ref "R32") (pin "2") (pinfunction "2_2") (pintype "passive"))
    )
    (net (code "52") (name "Net-(DS4-E)") (class "Default")
      (node (ref "DS4") (pin "5") (pinfunction "E_5") (pintype "passive"))
      (node (ref "R29") (pin "2") (pinfunction "2_2") (pintype "passive"))
    )
    (net (code "53") (name "Net-(DS4-F)") (class "Default")
      (node (ref "DS4") (pin "11") (pinfunction "F_11") (pintype "passive"))
      (node (ref "R30") (pin "2") (pinfunction "2_2") (pintype "passive"))
    )
    (net (code "54") (name "Net-(DS4-G)") (class "Default")
      (node (ref "DS4") (pin "15") (pinfunction "G_15") (pintype "passive"))
      (node (ref "R31") (pin "2") (pinfunction "2_2") (pintype "passive"))
    )
    (net (code "55") (name "Net-(DS5-A)") (class "Default")
      (node (ref "DS5") (pin "14") (pinfunction "A_14") (pintype "passive"))
      (node (ref "R33") (pin "2") (pinfunction "2_2") (pintype "passive"))
    )
    (net (code "56") (name "Net-(DS5-B)") (class "Default")
      (node (ref "DS5") (pin "16") (pinfunction "B_16") (pintype "passive"))
      (node (ref "R34") (pin "2") (pinfunction "2_2") (pintype "passive"))
    )
    (net (code "57") (name "Net-(DS5-C)") (class "Default")
      (node (ref "DS5") (pin "13") (pinfunction "C_13") (pintype "passive"))
      (node (ref "R35") (pin "2") (pinfunction "2_2") (pintype "passive"))
    )
    (net (code "58") (name "Net-(DS5-D)") (class "Default")
      (node (ref "DS5") (pin "3") (pinfunction "D_3") (pintype "passive"))
      (node (ref "R36") (pin "2") (pinfunction "2_2") (pintype "passive"))
    )
    (net (code "59") (name "Net-(DS5-DP)") (class "Default")
      (node (ref "DS5") (pin "7") (pinfunction "DP_7") (pintype "passive"))
      (node (ref "R40") (pin "2") (pinfunction "2_2") (pintype "passive"))
    )
    (net (code "60") (name "Net-(DS5-E)") (class "Default")
      (node (ref "DS5") (pin "5") (pinfunction "E_5") (pintype "passive"))
      (node (ref "R37") (pin "2") (pinfunction "2_2") (pintype "passive"))
    )
    (net (code "61") (name "Net-(DS5-F)") (class "Default")
      (node (ref "DS5") (pin "11") (pinfunction "F_11") (pintype "passive"))
      (node (ref "R38") (pin "2") (pinfunction "2_2") (pintype "passive"))
    )
    (net (code "62") (name "Net-(DS5-G)") (class "Default")
      (node (ref "DS5") (pin "15") (pinfunction "G_15") (pintype "passive"))
      (node (ref "R39") (pin "2") (pinfunction "2_2") (pintype "passive"))
    )
    (net (code "63") (name "Net-(DS6-A)") (class "Default")
      (node (ref "DS6") (pin "14") (pinfunction "A_14") (pintype "passive"))
      (node (ref "R41") (pin "2") (pinfunction "2_2") (pintype "passive"))
    )
    (net (code "64") (name "Net-(DS6-B)") (class "Default")
      (node (ref "DS6") (pin "16") (pinfunction "B_16") (pintype "passive"))
      (node (ref "R42") (pin "2") (pinfunction "2_2") (pintype "passive"))
    )
    (net (code "65") (name "Net-(DS6-C)") (class "Default")
      (node (ref "DS6") (pin "13") (pinfunction "C_13") (pintype "passive"))
      (node (ref "R43") (pin "2") (pinfunction "2_2") (pintype "passive"))
    )
    (net (code "66") (name "Net-(DS6-D)") (class "Default")
      (node (ref "DS6") (pin "3") (pinfunction "D_3") (pintype "passive"))
      (node (ref "R44") (pin "2") (pinfunction "2_2") (pintype "passive"))
    )
    (net (code "67") (name "Net-(DS6-DP)") (class "Default")
      (node (ref "DS6") (pin "7") (pinfunction "DP_7") (pintype "passive"))
      (node (ref "R48") (pin "2") (pinfunction "2_2") (pintype "passive"))
    )
    (net (code "68") (name "Net-(DS6-E)") (class "Default")
      (node (ref "DS6") (pin "5") (pinfunction "E_5") (pintype "passive"))
      (node (ref "R45") (pin "2") (pinfunction "2_2") (pintype "passive"))
    )
    (net (code "69") (name "Net-(DS6-F)") (class "Default")
      (node (ref "DS6") (pin "11") (pinfunction "F_11") (pintype "passive"))
      (node (ref "R46") (pin "2") (pinfunction "2_2") (pintype "passive"))
    )
    (net (code "70") (name "Net-(DS6-G)") (class "Default")
      (node (ref "DS6") (pin "15") (pinfunction "G_15") (pintype "passive"))
      (node (ref "R47") (pin "2") (pinfunction "2_2") (pintype "passive"))
    )
    (net (code "71") (name "Net-(IC1A-QA)") (class "Default")
      (node (ref "IC1") (pin "15") (pinfunction "QA_15") (pintype "tri_state"))
      (node (ref "R49") (pin "1") (pinfunction "1_1") (pintype "passive"))
    )
    (net (code "72") (name "Net-(IC1A-QB)") (class "Default")
      (node (ref "IC1") (pin "1") (pinfunction "QB_1") (pintype "tri_state"))
      (node (ref "R50") (pin "1") (pinfunction "1_1") (pintype "passive"))
    )
    (net (code "73") (name "Net-(IC1A-QC)") (class "Default")
      (node (ref "IC1") (pin "2") (pinfunction "QC_2") (pintype "tri_state"))
      (node (ref "R51") (pin "1") (pinfunction "1_1") (pintype "passive"))
    )
    (net (code "74") (name "Net-(IC1A-QD)") (class "Default")
      (node (ref "IC1") (pin "3") (pinfunction "QD_3") (pintype "tri_state"))
      (node (ref "R52") (pin "1") (pinfunction "1_1") (pintype "passive"))
    )
    (net (code "75") (name "Net-(IC1A-QE)") (class "Default")
      (node (ref "IC1") (pin "4") (pinfunction "QE_4") (pintype "tri_state"))
      (node (ref "R53") (pin "1") (pinfunction "1_1") (pintype "passive"))
    )
    (net (code "76") (name "Net-(IC1A-QF)") (class "Default")
      (node (ref "IC1") (pin "5") (pinfunction "QF_5") (pintype "tri_state"))
      (node (ref "R54") (pin "1") (pinfunction "1_1") (pintype "passive"))
    )
    (net (code "77") (name "Net-(IC1A-QG)") (class "Default")
      (node (ref "IC1") (pin "6") (pinfunction "QG_6") (pintype "tri_state"))
      (node (ref "R55") (pin "1") (pinfunction "1_1") (pintype "passive"))
    )
    (net (code "78") (name "Net-(IC1A-QH)") (class "Default")
      (node (ref "IC1") (pin "7") (pinfunction "QH_7") (pintype "tri_state"))
      (node (ref "R56") (pin "1") (pinfunction "1_1") (pintype "passive"))
    )
    (net (code "79") (name "Net-(IC1A-SER)") (class "Default")
      (node (ref "IC1") (pin "14") (pinfunction "SER_14") (pintype "input"))
      (node (ref "IC7") (pin "9") (pinfunction "QH*_9") (pintype "tri_state"))
    )
    (net (code "80") (name "Net-(IC2A-QA)") (class "Default")
      (node (ref "IC2") (pin "15") (pinfunction "QA_15") (pintype "tri_state"))
      (node (ref "R1") (pin "1") (pinfunction "1_1") (pintype "passive"))
    )
    (net (code "81") (name "Net-(IC2A-QB)") (class "Default")
      (node (ref "IC2") (pin "1") (pinfunction "QB_1") (pintype "tri_state"))
      (node (ref "R2") (pin "1") (pinfunction "1_1") (pintype "passive"))
    )
    (net (code "82") (name "Net-(IC2A-QC)") (class "Default")
      (node (ref "IC2") (pin "2") (pinfunction "QC_2") (pintype "tri_state"))
      (node (ref "R3") (pin "1") (pinfunction "1_1") (pintype "passive"))
    )
    (net (code "83") (name "Net-(IC2A-QD)") (class "Default")
      (node (ref "IC2") (pin "3") (pinfunction "QD_3") (pintype "tri_state"))
      (node (ref "R4") (pin "1") (pinfunction "1_1") (pintype "passive"))
    )
    (net (code "84") (name "Net-(IC2A-QE)") (class "Default")
      (node (ref "IC2") (pin "4") (pinfunction "QE_4") (pintype "tri_state"))
      (node (ref "R5") (pin "1") (pinfunction "1_1") (pintype "passive"))
    )
    (net (code "85") (name "Net-(IC2A-QF)") (class "Default")
      (node (ref "IC2") (pin "5") (pinfunction "QF_5") (pintype "tri_state"))
      (node (ref "R6") (pin "1") (pinfunction "1_1") (pintype "passive"))
    )
    (net (code "86") (name "Net-(IC2A-QG)") (class "Default")
      (node (ref "IC2") (pin "6") (pinfunction "QG_6") (pintype "tri_state"))
      (node (ref "R7") (pin "1") (pinfunction "1_1") (pintype "passive"))
    )
    (net (code "87") (name "Net-(IC2A-QH)") (class "Default")
      (node (ref "IC2") (pin "7") (pinfunction "QH_7") (pintype "tri_state"))
      (node (ref "R8") (pin "1") (pinfunction "1_1") (pintype "passive"))
    )
    (net (code "88") (name "Net-(IC2A-QH*)") (class "Default")
      (node (ref "IC2") (pin "9") (pinfunction "QH*_9") (pintype "tri_state"))
      (node (ref "IC5") (pin "14") (pinfunction "SER_14") (pintype "input"))
    )
    (net (code "89") (name "Net-(IC2A-SER)") (class "Default")
      (node (ref "IC2") (pin "14") (pinfunction "SER_14") (pintype "input"))
      (node (ref "IC3") (pin "9") (pinfunction "QH*_9") (pintype "tri_state"))
    )
    (net (code "90") (name "Net-(IC3A-QA)") (class "Default")
      (node (ref "IC3") (pin "15") (pinfunction "QA_15") (pintype "tri_state"))
      (node (ref "R9") (pin "1") (pinfunction "1_1") (pintype "passive"))
    )
    (net (code "91") (name "Net-(IC3A-QB)") (class "Default")
      (node (ref "IC3") (pin "1") (pinfunction "QB_1") (pintype "tri_state"))
      (node (ref "R10") (pin "1") (pinfunction "1_1") (pintype "passive"))
    )
    (net (code "92") (name "Net-(IC3A-QC)") (class "Default")
      (node (ref "IC3") (pin "2") (pinfunction "QC_2") (pintype "tri_state"))
      (node (ref "R11") (pin "1") (pinfunction "1_1") (pintype "passive"))
    )
    (net (code "93") (name "Net-(IC3A-QD)") (class "Default")
      (node (ref "IC3") (pin "3") (pinfunction "QD_3") (pintype "tri_state"))
      (node (ref "R12") (pin "1") (pinfunction "1_1") (pintype "passive"))
    )
    (net (code "94") (name "Net-(IC3A-QE)") (class "Default")
      (node (ref "IC3") (pin "4") (pinfunction "QE_4") (pintype "tri_state"))
      (node (ref "R13") (pin "1") (pinfunction "1_1") (pintype "passive"))
    )
    (net (code "95") (name "Net-(IC3A-QF)") (class "Default")
      (node (ref "IC3") (pin "5") (pinfunction "QF_5") (pintype "tri_state"))
      (node (ref "R14") (pin "1") (pinfunction "1_1") (pintype "passive"))
    )
    (net (code "96") (name "Net-(IC3A-QG)") (class "Default")
      (node (ref "IC3") (pin "6") (pinfunction "QG_6") (pintype "tri_state"))
      (node (ref "R15") (pin "1") (pinfunction "1_1") (pintype "passive"))
    )
    (net (code "97") (name "Net-(IC3A-QH)") (class "Default")
      (node (ref "IC3") (pin "7") (pinfunction "QH_7") (pintype "tri_state"))
      (node (ref "R16") (pin "1") (pinfunction "1_1") (pintype "passive"))
    )
    (net (code "98") (name "Net-(IC3A-SER)") (class "Default")
      (node (ref "IC3") (pin "14") (pinfunction "SER_14") (pintype "input"))
      (node (ref "IC4") (pin "9") (pinfunction "QH*_9") (pintype "tri_state"))
    )
    (net (code "99") (name "Net-(IC4A-QA)") (class "Default")
      (node (ref "IC4") (pin "15") (pinfunction "QA_15") (pintype "tri_state"))
      (node (ref "R17") (pin "1") (pinfunction "1_1") (pintype "passive"))
    )
    (net (code "100") (name "Net-(IC4A-QB)") (class "Default")
      (node (ref "IC4") (pin "1") (pinfunction "QB_1") (pintype "tri_state"))
      (node (ref "R18") (pin "1") (pinfunction "1_1") (pintype "passive"))
    )
    (net (code "101") (name "Net-(IC4A-QC)") (class "Default")
      (node (ref "IC4") (pin "2") (pinfunction "QC_2") (pintype "tri_state"))
      (node (ref "R19") (pin "1") (pinfunction "1_1") (pintype "passive"))
    )
    (net (code "102") (name "Net-(IC4A-QD)") (class "Default")
      (node (ref "IC4") (pin "3") (pinfunction "QD_3") (pintype "tri_state"))
      (node (ref "R20") (pin "1") (pinfunction "1_1") (pintype "passive"))
    )
    (net (code "103") (name "Net-(IC4A-QE)") (class "Default")
      (node (ref "IC4") (pin "4") (pinfunction "QE_4") (pintype "tri_state"))
      (node (ref "R21") (pin "1") (pinfunction "1_1") (pintype "passive"))
    )
    (net (code "104") (name "Net-(IC4A-QF)") (class "Default")
      (node (ref "IC4") (pin "5") (pinfunction "QF_5") (pintype "tri_state"))
      (node (ref "R22") (pin "1") (pinfunction "1_1") (pintype "passive"))
    )
    (net (code "105") (name "Net-(IC4A-QG)") (class "Default")
      (node (ref "IC4") (pin "6") (pinfunction "QG_6") (pintype "tri_state"))
      (node (ref "R23") (pin "1") (pinfunction "1_1") (pintype "passive"))
    )
    (net (code "106") (name "Net-(IC4A-QH)") (class "Default")
      (node (ref "IC4") (pin "7") (pinfunction "QH_7") (pintype "tri_state"))
      (node (ref "R24") (pin "1") (pinfunction "1_1") (pintype "passive"))
    )
    (net (code "107") (name "Net-(IC5A-QA)") (class "Default")
      (node (ref "IC5") (pin "15") (pinfunction "QA_15") (pintype "tri_state"))
      (node (ref "R25") (pin "1") (pinfunction "1_1") (pintype "passive"))
    )
    (net (code "108") (name "Net-(IC5A-QB)") (class "Default")
      (node (ref "IC5") (pin "1") (pinfunction "QB_1") (pintype "tri_state"))
      (node (ref "R26") (pin "1") (pinfunction "1_1") (pintype "passive"))
    )
    (net (code "109") (name "Net-(IC5A-QC)") (class "Default")
      (node (ref "IC5") (pin "2") (pinfunction "QC_2") (pintype "tri_state"))
      (node (ref "R27") (pin "1") (pinfunction "1_1") (pintype "passive"))
    )
    (net (code "110") (name "Net-(IC5A-QD)") (class "Default")
      (node (ref "IC5") (pin "3") (pinfunction "QD_3") (pintype "tri_state"))
      (node (ref "R28") (pin "1") (pinfunction "1_1") (pintype "passive"))
    )
    (net (code "111") (name "Net-(IC5A-QE)") (class "Default")
      (node (ref "IC5") (pin "4") (pinfunction "QE_4") (pintype "tri_state"))
      (node (ref "R29") (pin "1") (pinfunction "1_1") (pintype "passive"))
    )
    (net (code "112") (name "Net-(IC5A-QF)") (class "Default")
      (node (ref "IC5") (pin "5") (pinfunction "QF_5") (pintype "tri_state"))
      (node (ref "R30") (pin "1") (pinfunction "1_1") (pintype "passive"))
    )
    (net (code "113") (name "Net-(IC5A-QG)") (class "Default")
      (node (ref "IC5") (pin "6") (pinfunction "QG_6") (pintype "tri_state"))
      (node (ref "R31") (pin "1") (pinfunction "1_1") (pintype "passive"))
    )
    (net (code "114") (name "Net-(IC5A-QH)") (class "Default")
      (node (ref "IC5") (pin "7") (pinfunction "QH_7") (pintype "tri_state"))
      (node (ref "R32") (pin "1") (pinfunction "1_1") (pintype "passive"))
    )
    (net (code "115") (name "Net-(IC5A-QH*)") (class "Default")
      (node (ref "IC5") (pin "9") (pinfunction "QH*_9") (pintype "tri_state"))
      (node (ref "IC6") (pin "14") (pinfunction "SER_14") (pintype "input"))
    )
    (net (code "116") (name "Net-(IC6A-QA)") (class "Default")
      (node (ref "IC6") (pin "15") (pinfunction "QA_15") (pintype "tri_state"))
      (node (ref "R33") (pin "1") (pinfunction "1_1") (pintype "passive"))
    )
    (net (code "117") (name "Net-(IC6A-QB)") (class "Default")
      (node (ref "IC6") (pin "1") (pinfunction "QB_1") (pintype "tri_state"))
      (node (ref "R34") (pin "1") (pinfunction "1_1") (pintype "passive"))
    )
    (net (code "118") (name "Net-(IC6A-QC)") (class "Default")
      (node (ref "IC6") (pin "2") (pinfunction "QC_2") (pintype "tri_state"))
      (node (ref "R35") (pin "1") (pinfunction "1_1") (pintype "passive"))
    )
    (net (code "119") (name "Net-(IC6A-QD)") (class "Default")
      (node (ref "IC6") (pin "3") (pinfunction "QD_3") (pintype "tri_state"))
      (node (ref "R36") (pin "1") (pinfunction "1_1") (pintype "passive"))
    )
    (net (code "120") (name "Net-(IC6A-QE)") (class "Default")
      (node (ref "IC6") (pin "4") (pinfunction "QE_4") (pintype "tri_state"))
      (node (ref "R37") (pin "1") (pinfunction "1_1") (pintype "passive"))
    )
    (net (code "121") (name "Net-(IC6A-QF)") (class "Default")
      (node (ref "IC6") (pin "5") (pinfunction "QF_5") (pintype "tri_state"))
      (node (ref "R38") (pin "1") (pinfunction "1_1") (pintype "passive"))
    )
    (net (code "122") (name "Net-(IC6A-QG)") (class "Default")
      (node (ref "IC6") (pin "6") (pinfunction "QG_6") (pintype "tri_state"))
      (node (ref "R39") (pin "1") (pinfunction "1_1") (pintype "passive"))
    )
    (net (code "123") (name "Net-(IC6A-QH)") (class "Default")
      (node (ref "IC6") (pin "7") (pinfunction "QH_7") (pintype "tri_state"))
      (node (ref "R40") (pin "1") (pinfunction "1_1") (pintype "passive"))
    )
    (net (code "124") (name "Net-(IC6A-QH*)") (class "Default")
      (node (ref "IC6") (pin "9") (pinfunction "QH*_9") (pintype "tri_state"))
      (node (ref "IC7") (pin "14") (pinfunction "SER_14") (pintype "input"))
    )
    (net (code "125") (name "Net-(IC7A-QA)") (class "Default")
      (node (ref "IC7") (pin "15") (pinfunction "QA_15") (pintype "tri_state"))
      (node (ref "R41") (pin "1") (pinfunction "1_1") (pintype "passive"))
    )
    (net (code "126") (name "Net-(IC7A-QB)") (class "Default")
      (node (ref "IC7") (pin "1") (pinfunction "QB_1") (pintype "tri_state"))
      (node (ref "R42") (pin "1") (pinfunction "1_1") (pintype "passive"))
    )
    (net (code "127") (name "Net-(IC7A-QC)") (class "Default")
      (node (ref "IC7") (pin "2") (pinfunction "QC_2") (pintype "tri_state"))
      (node (ref "R43") (pin "1") (pinfunction "1_1") (pintype "passive"))
    )
    (net (code "128") (name "Net-(IC7A-QD)") (class "Default")
      (node (ref "IC7") (pin "3") (pinfunction "QD_3") (pintype "tri_state"))
      (node (ref "R44") (pin "1") (pinfunction "1_1") (pintype "passive"))
    )
    (net (code "129") (name "Net-(IC7A-QE)") (class "Default")
      (node (ref "IC7") (pin "4") (pinfunction "QE_4") (pintype "tri_state"))
      (node (ref "R45") (pin "1") (pinfunction "1_1") (pintype "passive"))
    )
    (net (code "130") (name "Net-(IC7A-QF)") (class "Default")
      (node (ref "IC7") (pin "5") (pinfunction "QF_5") (pintype "tri_state"))
      (node (ref "R46") (pin "1") (pinfunction "1_1") (pintype "passive"))
    )
    (net (code "131") (name "Net-(IC7A-QG)") (class "Default")
      (node (ref "IC7") (pin "6") (pinfunction "QG_6") (pintype "tri_state"))
      (node (ref "R47") (pin "1") (pinfunction "1_1") (pintype "passive"))
    )
    (net (code "132") (name "Net-(IC7A-QH)") (class "Default")
      (node (ref "IC7") (pin "7") (pinfunction "QH_7") (pintype "tri_state"))
      (node (ref "R48") (pin "1") (pinfunction "1_1") (pintype "passive"))
    )
    (net (code "133") (name "Net-(JP1-Pad2)") (class "Default")
      (node (ref "JP1") (pin "2") (pinfunction "2_2") (pintype "passive"))
      (node (ref "R60") (pin "2") (pinfunction "2_2") (pintype "passive"))
    )
    (net (code "134") (name "Net-(RST-S)") (class "Default")
      (node (ref "R57") (pin "1") (pinfunction "1_1") (pintype "passive"))
      (node (ref "RST") (pin "1") (pinfunction "S_1") (pintype "passive"))
      (node (ref "RST") (pin "2") (pinfunction "S1_2") (pintype "passive"))
      (node (ref "U1") (pin "7") (pinfunction "NRST_7") (pintype "bidirectional"))
    )
    (net (code "135") (name "Net-(U1-BOOT0)") (class "Default")
      (node (ref "BOOT0") (pin "2") (pinfunction "2_2") (pintype "passive"))
      (node (ref "U1") (pin "60") (pinfunction "BOOT0_60") (pintype "input"))
    )
    (net (code "136") (name "Net-(U1-PD0-OSC_IN)") (class "Default")
      (node (ref "C10") (pin "1") (pinfunction "1_1") (pintype "passive"))
      (node (ref "Q1") (pin "1") (pinfunction "1_1") (pintype "passive"))
      (node (ref "U1") (pin "5") (pinfunction "PD0-OSC_IN_5") (pintype "bidirectional"))
    )
    (net (code "137") (name "Net-(U1-PD1-OSC_OUT)") (class "Default")
      (node (ref "C11") (pin "1") (pinfunction "1_1") (pintype "passive"))
      (node (ref "Q1") (pin "2") (pinfunction "2_2") (pintype "passive"))
      (node (ref "U1") (pin "6") (pinfunction "PD1-OSC_OUT_6") (pintype "bidirectional"))
    )
    (net (code "138") (name "Net-(U3-CANH)") (class "Default")
      (node (ref "CAN") (pin "1") (pinfunction "1_1") (pintype "passive"))
      (node (ref "D1") (pin "1") (pinfunction "1_1") (pintype "passive"))
      (node (ref "JP1") (pin "1") (pinfunction "1_1") (pintype "passive"))
      (node (ref "U3") (pin "7") (pinfunction "CANH_7") (pintype "bidirectional"))
    )
    (net (code "139") (name "Net-(U3-CANL)") (class "Default")
      (node (ref "CAN") (pin "2") (pinfunction "2_2") (pintype "passive"))
      (node (ref "D1") (pin "2") (pinfunction "2_2") (pintype "passive"))
      (node (ref "R60") (pin "1") (pinfunction "1_1") (pintype "passive"))
      (node (ref "U3") (pin "6") (pinfunction "CANL_6") (pintype "bidirectional"))
    )
    (net (code "140") (name "PWM") (class "Default")
      (node (ref "U1") (pin "50") (pinfunction "PA15_50") (pintype "bidirectional"))
      (node (ref "U2") (pin "2") (pinfunction "A1_2") (pintype "bidirectional"))
    )
    (net (code "141") (name "RCK") (class "Default")
      (node (ref "IC1") (pin "12") (pinfunction "RCK_12") (pintype "input"))
      (node (ref "IC2") (pin "12") (pinfunction "RCK_12") (pintype "input"))
      (node (ref "IC3") (pin "12") (pinfunction "RCK_12") (pintype "input"))
      (node (ref "IC4") (pin "12") (pinfunction "RCK_12") (pintype "input"))
      (node (ref "IC5") (pin "12") (pinfunction "RCK_12") (pintype "input"))
      (node (ref "IC6") (pin "12") (pinfunction "RCK_12") (pintype "input"))
      (node (ref "IC7") (pin "12") (pinfunction "RCK_12") (pintype "input"))
      (node (ref "U2") (pin "11") (pinfunction "B3_11") (pintype "bidirectional"))
    )
    (net (code "142") (name "RCK_STM") (class "Default")
      (node (ref "U1") (pin "20") (pinfunction "PA4_20") (pintype "bidirectional"))
      (node (ref "U2") (pin "4") (pinfunction "A3_4") (pintype "bidirectional"))
    )
    (net (code "143") (name "SCK") (class "Default")
      (node (ref "IC1") (pin "11") (pinfunction "SCK_11") (pintype "input"))
      (node (ref "IC2") (pin "11") (pinfunction "SCK_11") (pintype "input"))
      (node (ref "IC3") (pin "11") (pinfunction "SCK_11") (pintype "input"))
      (node (ref "IC4") (pin "11") (pinfunction "SCK_11") (pintype "input"))
      (node (ref "IC5") (pin "11") (pinfunction "SCK_11") (pintype "input"))
      (node (ref "IC6") (pin "11") (pinfunction "SCK_11") (pintype "input"))
      (node (ref "IC7") (pin "11") (pinfunction "SCK_11") (pintype "input"))
      (node (ref "U2") (pin "12") (pinfunction "B2_12") (pintype "bidirectional"))
    )
    (net (code "144") (name "SDI") (class "Default")
      (node (ref "IC4") (pin "14") (pinfunction "SER_14") (pintype "input"))
      (node (ref "U2") (pin "10") (pinfunction "B4_10") (pintype "bidirectional"))
    )
    (net (code "145") (name "SPI_MOSI") (class "Default")
      (node (ref "U1") (pin "23") (pinfunction "PA7_23") (pintype "bidirectional"))
      (node (ref "U2") (pin "5") (pinfunction "A4_5") (pintype "bidirectional"))
    )
    (net (code "146") (name "SPI_SCK") (class "Default")
      (node (ref "U1") (pin "21") (pinfunction "PA5_21") (pintype "bidirectional"))
      (node (ref "U2") (pin "3") (pinfunction "A2_3") (pintype "bidirectional"))
    )
    (net (code "147") (name "SWCLK") (class "Default")
      (node (ref "DEBUG") (pin "2") (pinfunction "2_2") (pintype "passive"))
      (node (ref "U1") (pin "49") (pinfunction "PA14_49") (pintype "bidirectional"))
    )
    (net (code "148") (name "SWDIO") (class "Default")
      (node (ref "DEBUG") (pin "3") (pinfunction "3_3") (pintype "passive"))
      (node (ref "U1") (pin "46") (pinfunction "PA13_46") (pintype "bidirectional"))
    )
    (net (code "149") (name "unconnected-(CN1-PadD+)") (class "Default")
      (node (ref "CN1") (pin "D+") (pinfunction "D+_D+") (pintype "bidirectional"))
    )
    (net (code "150") (name "unconnected-(CN1-PadD-)") (class "Default")
      (node (ref "CN1") (pin "D-") (pinfunction "D-_D-") (pintype "bidirectional"))
    )
    (net (code "151") (name "unconnected-(CN1-PadID)") (class "Default")
      (node (ref "CN1") (pin "ID") (pinfunction "ID_ID") (pintype "bidirectional"))
    )
    (net (code "152") (name "unconnected-(DS1-L1_L2-Pad12)") (class "Default")
      (node (ref "DS1") (pin "12") (pinfunction "L1_L2_12") (pintype "passive"))
    )
    (net (code "153") (name "unconnected-(DS1-L3-Pad9)") (class "Default")
      (node (ref "DS1") (pin "9") (pinfunction "L3_9") (pintype "passive"))
    )
    (net (code "154") (name "unconnected-(DS1-Pad4)") (class "Default")
      (node (ref "DS1") (pin "4") (pinfunction "4_4") (pintype "passive"))
    )
    (net (code "155") (name "unconnected-(DS1-Pad10)") (class "Default")
      (node (ref "DS1") (pin "10") (pinfunction "10_10") (pintype "passive"))
    )
    (net (code "156") (name "unconnected-(DS2-L1_L2-Pad12)") (class "Default")
      (node (ref "DS2") (pin "12") (pinfunction "L1_L2_12") (pintype "passive"))
    )
    (net (code "157") (name "unconnected-(DS2-L3-Pad9)") (class "Default")
      (node (ref "DS2") (pin "9") (pinfunction "L3_9") (pintype "passive"))
    )
    (net (code "158") (name "unconnected-(DS2-Pad4)") (class "Default")
      (node (ref "DS2") (pin "4") (pinfunction "4_4") (pintype "passive"))
    )
    (net (code "159") (name "unconnected-(DS2-Pad10)") (class "Default")
      (node (ref "DS2") (pin "10") (pinfunction "10_10") (pintype "passive"))
    )
    (net (code "160") (name "unconnected-(DS3-L1_L2-Pad12)") (class "Default")
      (node (ref "DS3") (pin "12") (pinfunction "L1_L2_12") (pintype "passive"))
    )
    (net (code "161") (name "unconnected-(DS3-L3-Pad9)") (class "Default")
      (node (ref "DS3") (pin "9") (pinfunction "L3_9") (pintype "passive"))
    )
    (net (code "162") (name "unconnected-(DS3-Pad4)") (class "Default")
      (node (ref "DS3") (pin "4") (pinfunction "4_4") (pintype "passive"))
    )
    (net (code "163") (name "unconnected-(DS3-Pad10)") (class "Default")
      (node (ref "DS3") (pin "10") (pinfunction "10_10") (pintype "passive"))
    )
    (net (code "164") (name "unconnected-(DS4-L1_L2-Pad12)") (class "Default")
      (node (ref "DS4") (pin "12") (pinfunction "L1_L2_12") (pintype "passive"))
    )
    (net (code "165") (name "unconnected-(DS4-L3-Pad9)") (class "Default")
      (node (ref "DS4") (pin "9") (pinfunction "L3_9") (pintype "passive"))
    )
    (net (code "166") (name "unconnected-(DS4-Pad4)") (class "Default")
      (node (ref "DS4") (pin "4") (pinfunction "4_4") (pintype "passive"))
    )
    (net (code "167") (name "unconnected-(DS4-Pad10)") (class "Default")
      (node (ref "DS4") (pin "10") (pinfunction "10_10") (pintype "passive"))
    )
    (net (code "168") (name "unconnected-(DS5-L1_L2-Pad12)") (class "Default")
      (node (ref "DS5") (pin "12") (pinfunction "L1_L2_12") (pintype "passive"))
    )
    (net (code "169") (name "unconnected-(DS5-L3-Pad9)") (class "Default")
      (node (ref "DS5") (pin "9") (pinfunction "L3_9") (pintype "passive"))
    )
    (net (code "170") (name "unconnected-(DS5-Pad4)") (class "Default")
      (node (ref "DS5") (pin "4") (pinfunction "4_4") (pintype "passive"))
    )
    (net (code "171") (name "unconnected-(DS5-Pad10)") (class "Default")
      (node (ref "DS5") (pin "10") (pinfunction "10_10") (pintype "passive"))
    )
    (net (code "172") (name "unconnected-(DS6-L1_L2-Pad12)") (class "Default")
      (node (ref "DS6") (pin "12") (pinfunction "L1_L2_12") (pintype "passive"))
    )
    (net (code "173") (name "unconnected-(DS6-L3-Pad9)") (class "Default")
      (node (ref "DS6") (pin "9") (pinfunction "L3_9") (pintype "passive"))
    )
    (net (code "174") (name "unconnected-(DS6-Pad4)") (class "Default")
      (node (ref "DS6") (pin "4") (pinfunction "4_4") (pintype "passive"))
    )
    (net (code "175") (name "unconnected-(DS6-Pad10)") (class "Default")
      (node (ref "DS6") (pin "10") (pinfunction "10_10") (pintype "passive"))
    )
    (net (code "176") (name "unconnected-(IC1A-QH*-Pad9)") (class "Default")
      (node (ref "IC1") (pin "9") (pinfunction "QH*_9") (pintype "tri_state"))
    )
    (net (code "177") (name "unconnected-(U1-PA1-Pad15)") (class "Default")
      (node (ref "U1") (pin "15") (pinfunction "PA1_15") (pintype "bidirectional"))
    )
    (net (code "178") (name "unconnected-(U1-PA2-Pad16)") (class "Default")
      (node (ref "U1") (pin "16") (pinfunction "PA2_16") (pintype "bidirectional"))
    )
    (net (code "179") (name "unconnected-(U1-PA3-Pad17)") (class "Default")
      (node (ref "U1") (pin "17") (pinfunction "PA3_17") (pintype "bidirectional"))
    )
    (net (code "180") (name "unconnected-(U1-PA6-Pad22)") (class "Default")
      (node (ref "U1") (pin "22") (pinfunction "PA6_22") (pintype "bidirectional"))
    )
    (net (code "181") (name "unconnected-(U1-PA8-Pad41)") (class "Default")
      (node (ref "U1") (pin "41") (pinfunction "PA8_41") (pintype "bidirectional"))
    )
    (net (code "182") (name "unconnected-(U1-PA9-Pad42)") (class "Default")
      (node (ref "U1") (pin "42") (pinfunction "PA9_42") (pintype "bidirectional"))
    )
    (net (code "183") (name "unconnected-(U1-PA10-Pad43)") (class "Default")
      (node (ref "U1") (pin "43") (pinfunction "PA10_43") (pintype "bidirectional"))
    )
    (net (code "184") (name "unconnected-(U1-PA11-Pad44)") (class "Default")
      (node (ref "U1") (pin "44") (pinfunction "PA11_44") (pintype "bidirectional"))
    )
    (net (code "185") (name "unconnected-(U1-PA12-Pad45)") (class "Default")
      (node (ref "U1") (pin "45") (pinfunction "PA12_45") (pintype "bidirectional"))
    )
    (net (code "186") (name "unconnected-(U1-PB0-Pad26)") (class "Default")
      (node (ref "U1") (pin "26") (pinfunction "PB0_26") (pintype "bidirectional"))
    )
    (net (code "187") (name "unconnected-(U1-PB1-Pad27)") (class "Default")
      (node (ref "U1") (pin "27") (pinfunction "PB1_27") (pintype "bidirectional"))
    )
    (net (code "188") (name "unconnected-(U1-PB2-Pad28)") (class "Default")
      (node (ref "U1") (pin "28") (pinfunction "PB2_28") (pintype "bidirectional"))
    )
    (net (code "189") (name "unconnected-(U1-PB3-Pad55)") (class "Default")
      (node (ref "U1") (pin "55") (pinfunction "PB3_55") (pintype "bidirectional"))
    )
    (net (code "190") (name "unconnected-(U1-PB4-Pad56)") (class "Default")
      (node (ref "U1") (pin "56") (pinfunction "PB4_56") (pintype "bidirectional"))
    )
    (net (code "191") (name "unconnected-(U1-PB5-Pad57)") (class "Default")
      (node (ref "U1") (pin "57") (pinfunction "PB5_57") (pintype "bidirectional"))
    )
    (net (code "192") (name "unconnected-(U1-PB6-Pad58)") (class "Default")
      (node (ref "U1") (pin "58") (pinfunction "PB6_58") (pintype "bidirectional"))
    )
    (net (code "193") (name "unconnected-(U1-PB7-Pad59)") (class "Default")
      (node (ref "U1") (pin "59") (pinfunction "PB7_59") (pintype "bidirectional"))
    )
    (net (code "194") (name "unconnected-(U1-PB10-Pad29)") (class "Default")
      (node (ref "U1") (pin "29") (pinfunction "PB10_29") (pintype "bidirectional"))
    )
    (net (code "195") (name "unconnected-(U1-PB11-Pad30)") (class "Default")
      (node (ref "U1") (pin "30") (pinfunction "PB11_30") (pintype "bidirectional"))
    )
    (net (code "196") (name "unconnected-(U1-PB12-Pad33)") (class "Default")
      (node (ref "U1") (pin "33") (pinfunction "PB12_33") (pintype "bidirectional"))
    )
    (net (code "197") (name "unconnected-(U1-PB13-Pad34)") (class "Default")
      (node (ref "U1") (pin "34") (pinfunction "PB13_34") (pintype "bidirectional"))
    )
    (net (code "198") (name "unconnected-(U1-PB14-Pad35)") (class "Default")
      (node (ref "U1") (pin "35") (pinfunction "PB14_35") (pintype "bidirectional"))
    )
    (net (code "199") (name "unconnected-(U1-PB15-Pad36)") (class "Default")
      (node (ref "U1") (pin "36") (pinfunction "PB15_36") (pintype "bidirectional"))
    )
    (net (code "200") (name "unconnected-(U1-PC0-Pad8)") (class "Default")
      (node (ref "U1") (pin "8") (pinfunction "PC0_8") (pintype "bidirectional"))
    )
    (net (code "201") (name "unconnected-(U1-PC1-Pad9)") (class "Default")
      (node (ref "U1") (pin "9") (pinfunction "PC1_9") (pintype "bidirectional"))
    )
    (net (code "202") (name "unconnected-(U1-PC2-Pad10)") (class "Default")
      (node (ref "U1") (pin "10") (pinfunction "PC2_10") (pintype "bidirectional"))
    )
    (net (code "203") (name "unconnected-(U1-PC3-Pad11)") (class "Default")
      (node (ref "U1") (pin "11") (pinfunction "PC3_11") (pintype "bidirectional"))
    )
    (net (code "204") (name "unconnected-(U1-PC4-Pad24)") (class "Default")
      (node (ref "U1") (pin "24") (pinfunction "PC4_24") (pintype "bidirectional"))
    )
    (net (code "205") (name "unconnected-(U1-PC5-Pad25)") (class "Default")
      (node (ref "U1") (pin "25") (pinfunction "PC5_25") (pintype "bidirectional"))
    )
    (net (code "206") (name "unconnected-(U1-PC6-Pad37)") (class "Default")
      (node (ref "U1") (pin "37") (pinfunction "PC6_37") (pintype "bidirectional"))
    )
    (net (code "207") (name "unconnected-(U1-PC7-Pad38)") (class "Default")
      (node (ref "U1") (pin "38") (pinfunction "PC7_38") (pintype "bidirectional"))
    )
    (net (code "208") (name "unconnected-(U1-PC8-Pad39)") (class "Default")
      (node (ref "U1") (pin "39") (pinfunction "PC8_39") (pintype "bidirectional"))
    )
    (net (code "209") (name "unconnected-(U1-PC9-Pad40)") (class "Default")
      (node (ref "U1") (pin "40") (pinfunction "PC9_40") (pintype "bidirectional"))
    )
    (net (code "210") (name "unconnected-(U1-PC10-Pad51)") (class "Default")
      (node (ref "U1") (pin "51") (pinfunction "PC10_51") (pintype "bidirectional"))
    )
    (net (code "211") (name "unconnected-(U1-PC11-Pad52)") (class "Default")
      (node (ref "U1") (pin "52") (pinfunction "PC11_52") (pintype "bidirectional"))
    )
    (net (code "212") (name "unconnected-(U1-PC12-Pad53)") (class "Default")
      (node (ref "U1") (pin "53") (pinfunction "PC12_53") (pintype "bidirectional"))
    )
    (net (code "213") (name "unconnected-(U1-PC13-TAMPER-RTC-Pad2)") (class "Default")
      (node (ref "U1") (pin "2") (pinfunction "PC13-TAMPER-RTC_2") (pintype "bidirectional"))
    )
    (net (code "214") (name "unconnected-(U1-PC14-OSC32_IN-Pad3)") (class "Default")
      (node (ref "U1") (pin "3") (pinfunction "PC14-OSC32_IN_3") (pintype "bidirectional"))
    )
    (net (code "215") (name "unconnected-(U1-PC15-OSC32_OUT-Pad4)") (class "Default")
      (node (ref "U1") (pin "4") (pinfunction "PC15-OSC32_OUT_4") (pintype "bidirectional"))
    )
    (net (code "216") (name "unconnected-(U1-PD2-Pad54)") (class "Default")
      (node (ref "U1") (pin "54") (pinfunction "PD2_54") (pintype "bidirectional"))
    )
    (net (code "217") (name "unconnected-(U2-NC-Pad9)") (class "Default")
      (node (ref "U2") (pin "9") (pinfunction "NC_9") (pintype "passive"))
    )
    (net (code "218") (name "unconnected-(U2-NC_2-Pad6)") (class "Default")
      (node (ref "U2") (pin "6") (pinfunction "NC_2_6") (pintype "passive"))
    )
    (net (code "219") (name "unconnected-(U4-NC-Pad4)") (class "Default")
      (node (ref "U4") (pin "4") (pinfunction "NC_4") (pintype "input"))
    )
    (net (code "220") (name "~{OE}") (class "Default")
      (node (ref "IC1") (pin "13") (pinfunction "G_13") (pintype "input"))
      (node (ref "U2") (pin "13") (pinfunction "B1_13") (pintype "bidirectional"))
    )
  )
)
